# ACB-Light-R1_0-J02.net
KiCad netlist of a schematic drawn in EAGLE
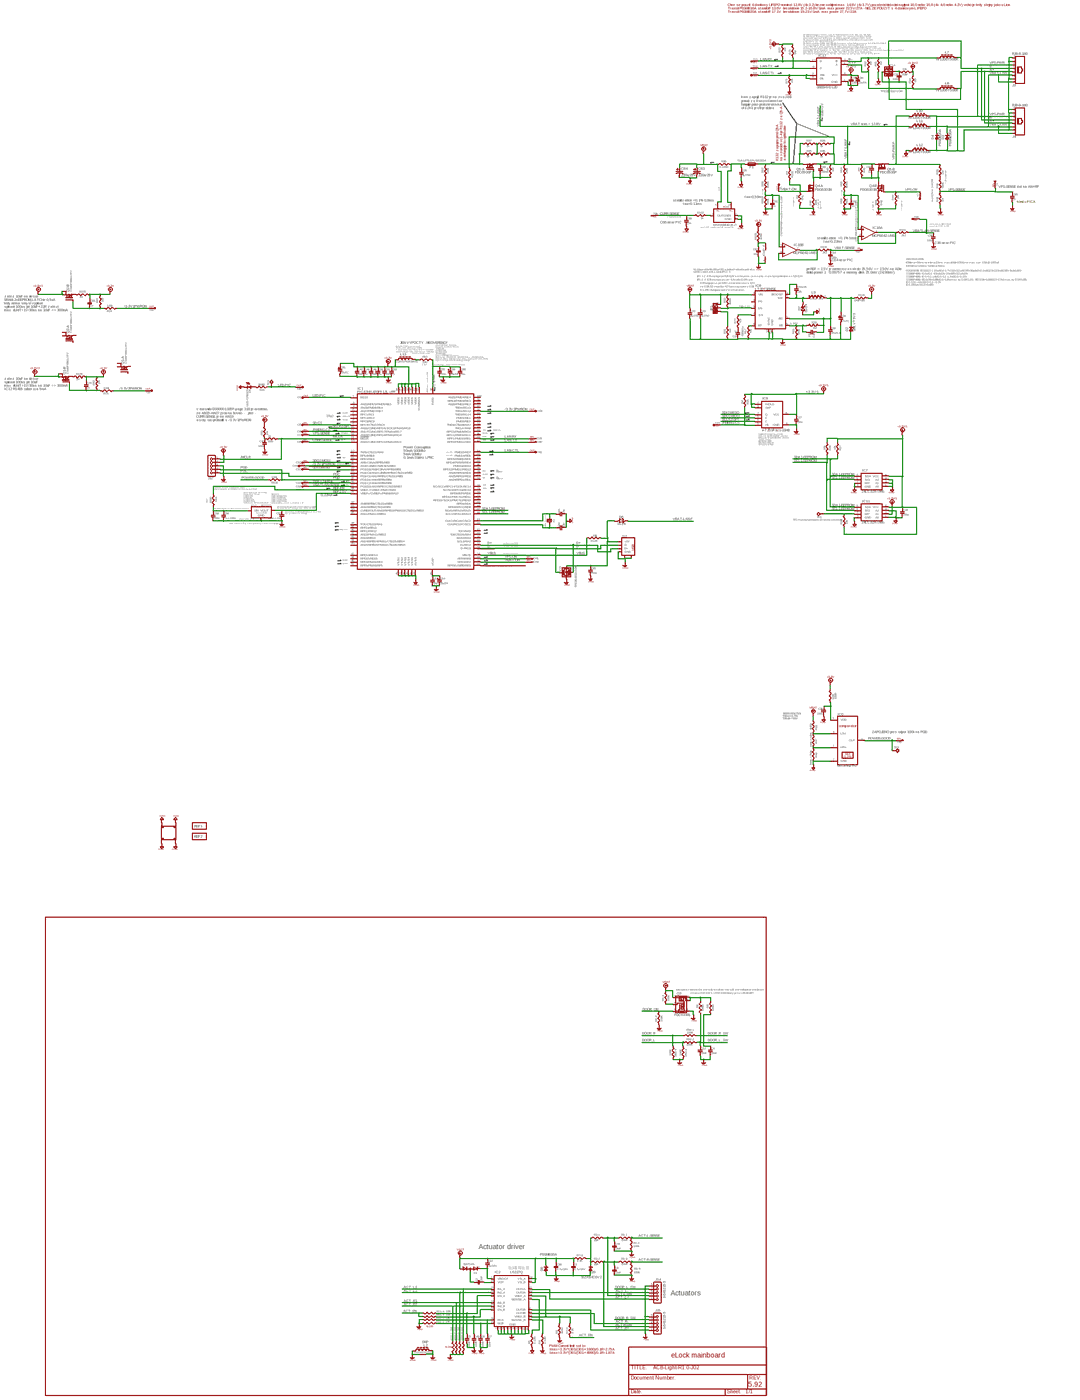
[diagram p0: schematic, sheet 1, overview]
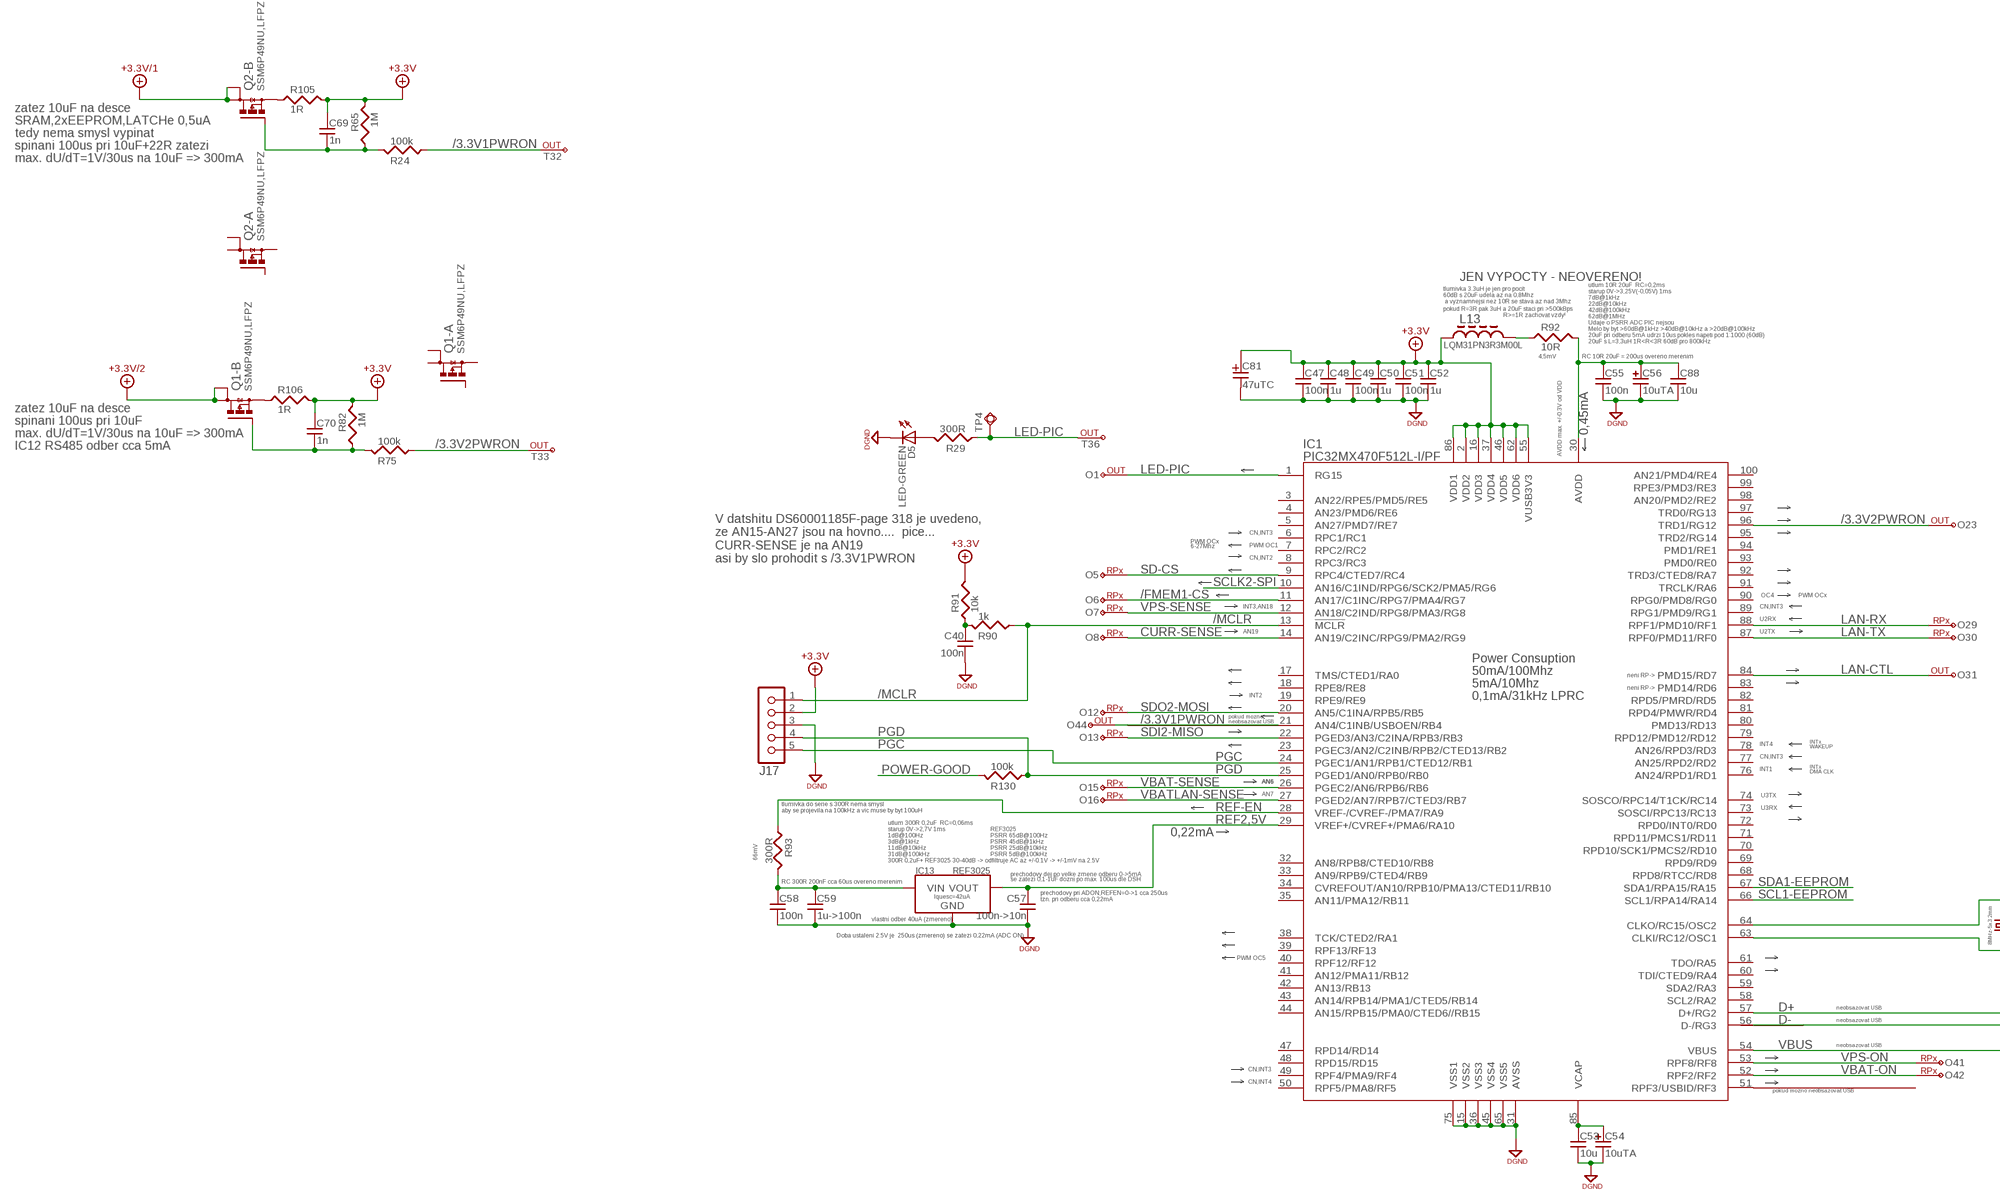
[diagram p1: schematic, sheet 1, part 1 of 5]
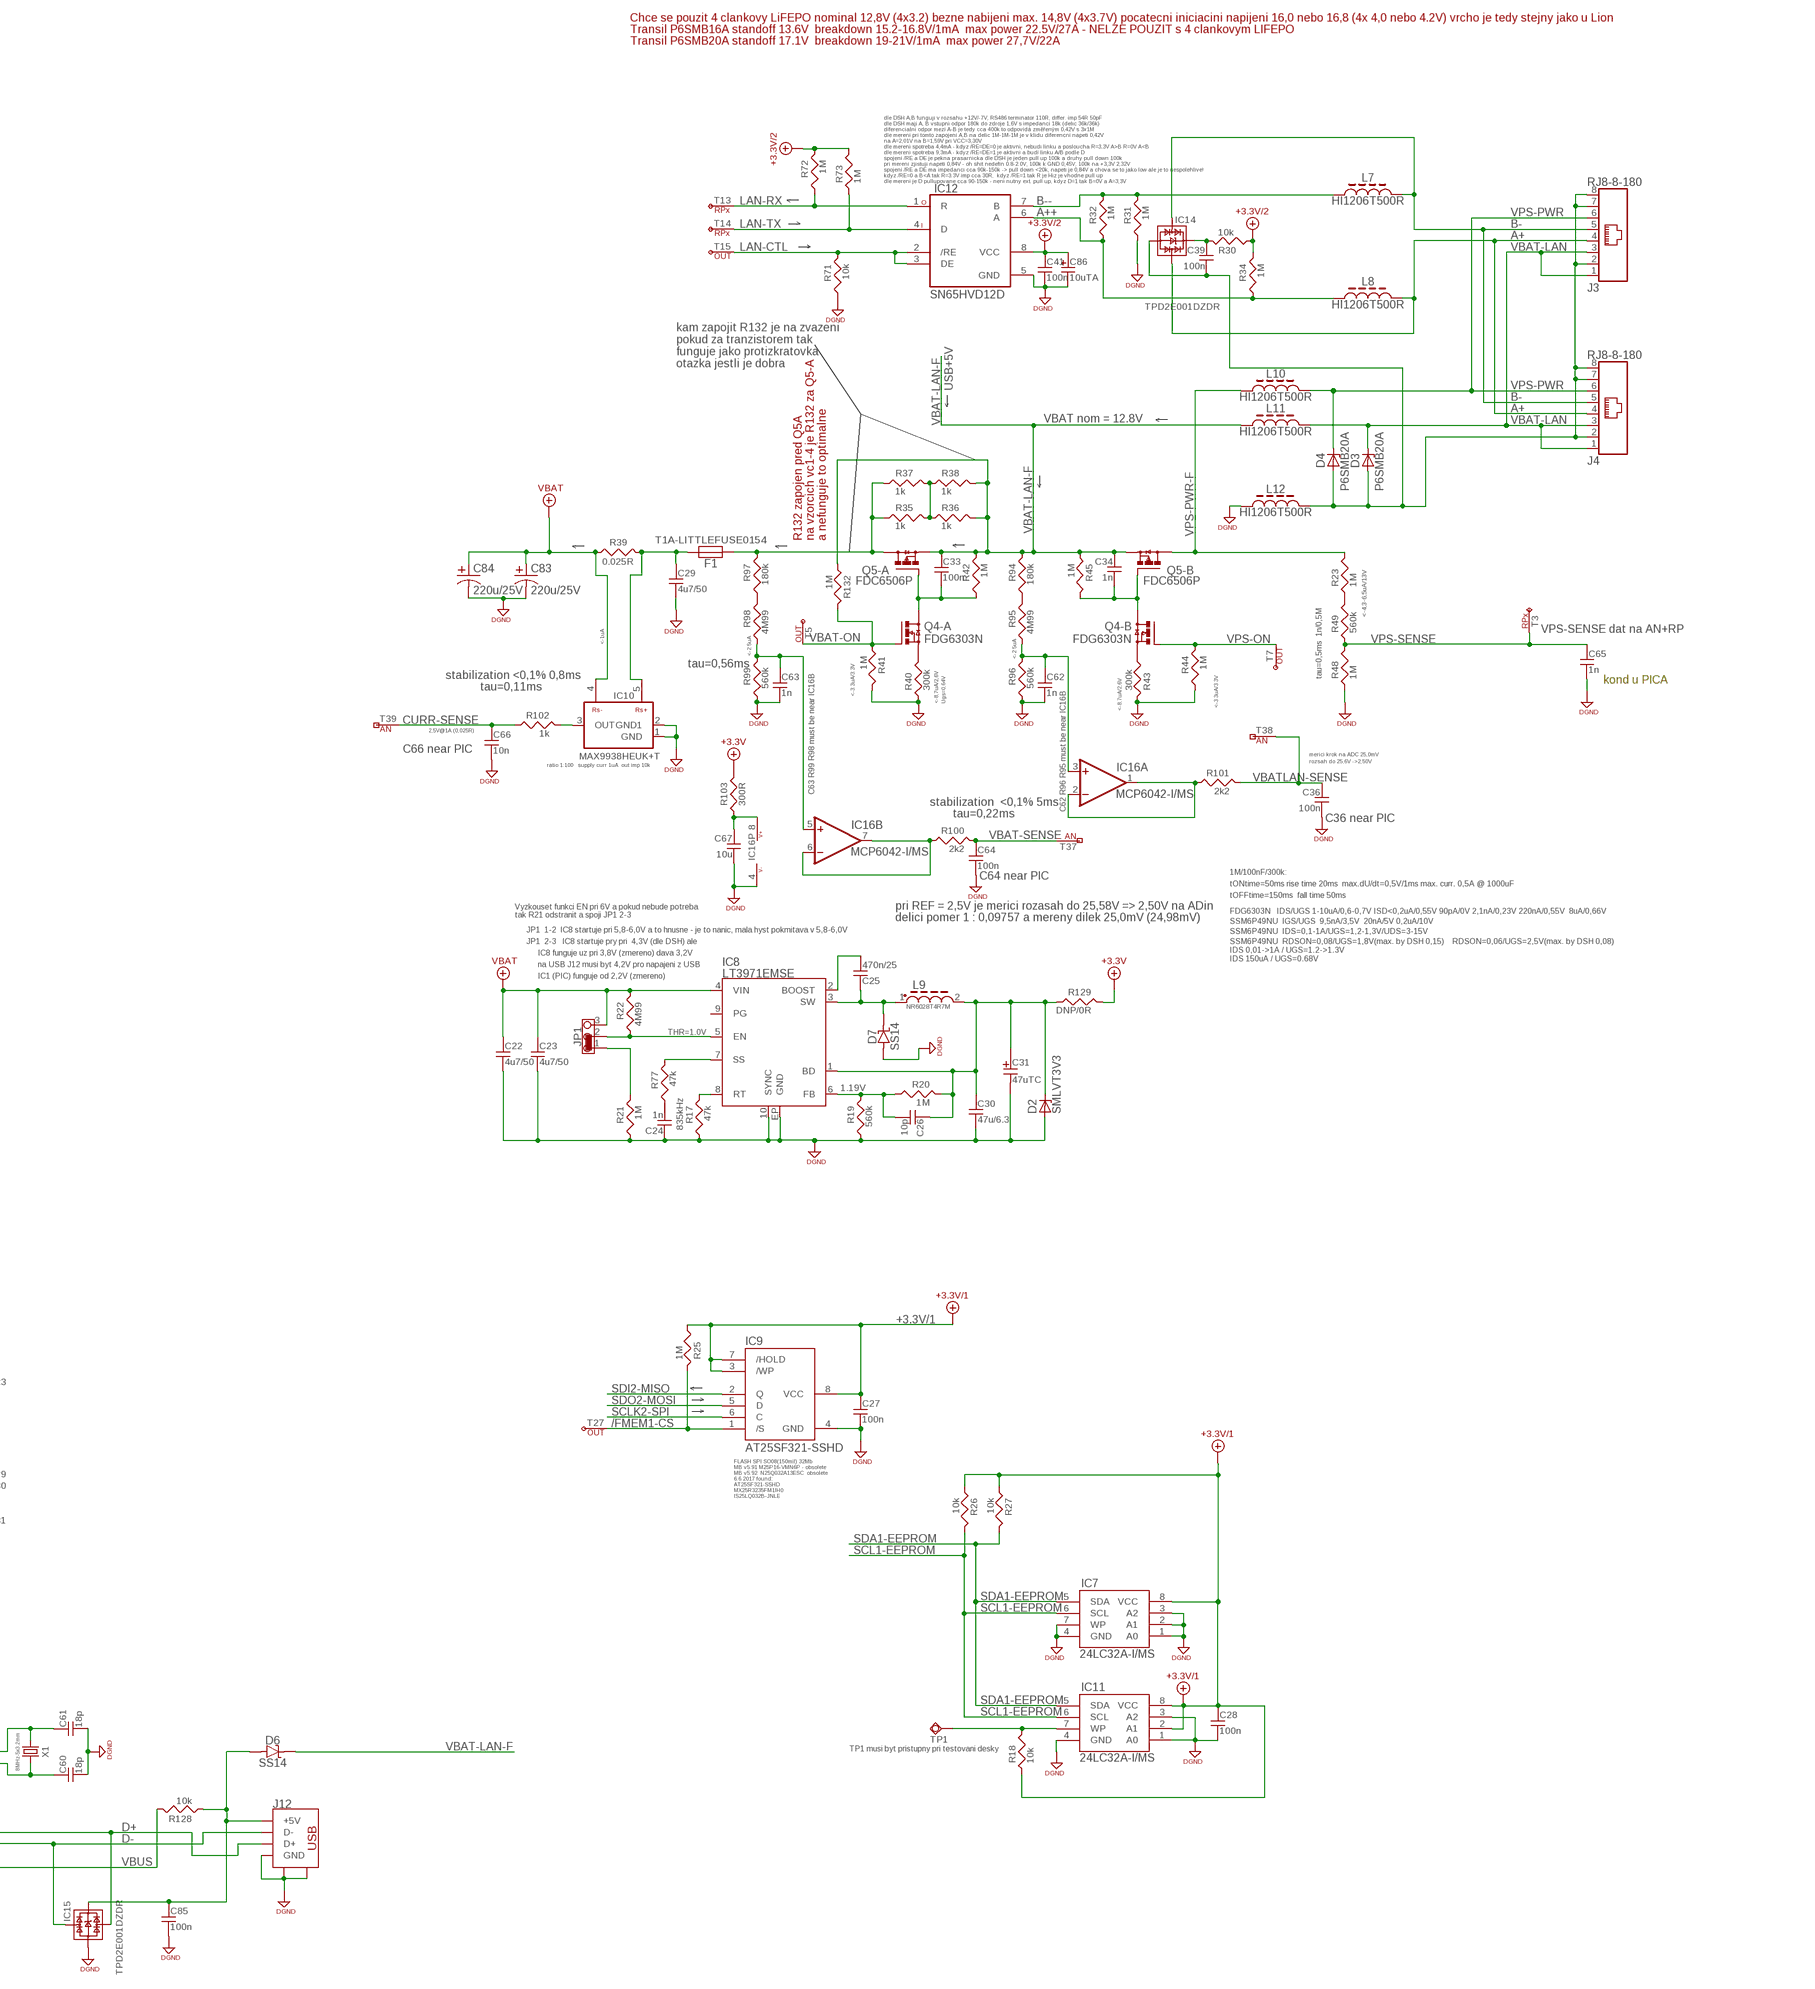
[diagram p2: schematic, sheet 1, part 2 of 5]
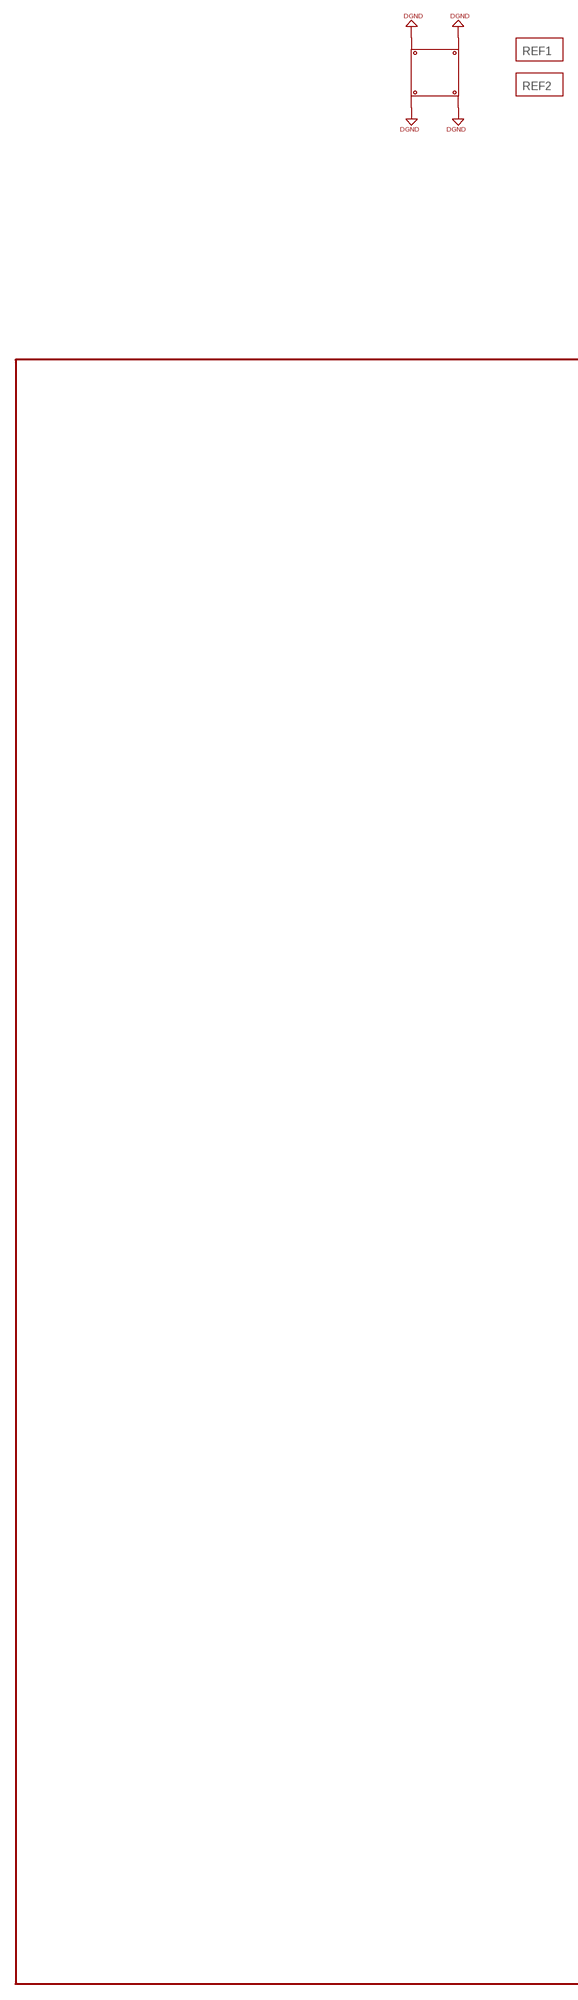
[diagram p3: schematic, sheet 1, part 3 of 5]
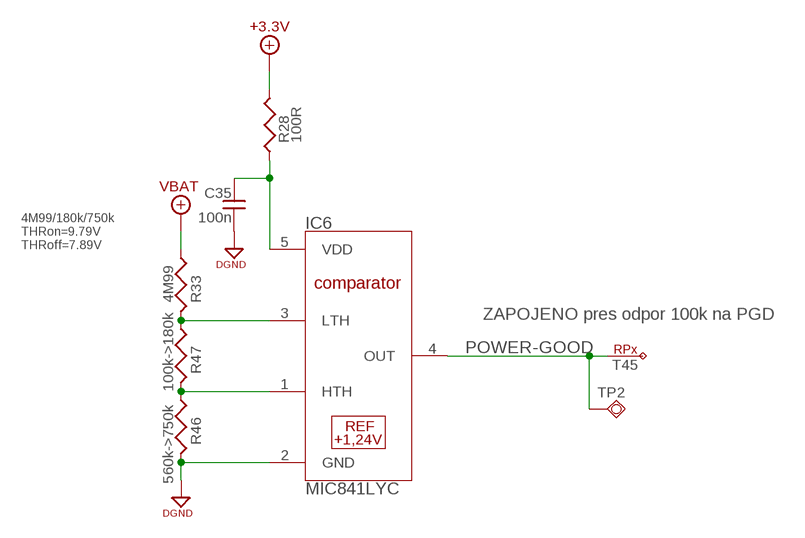
[diagram p4: schematic, sheet 1, part 4 of 5]
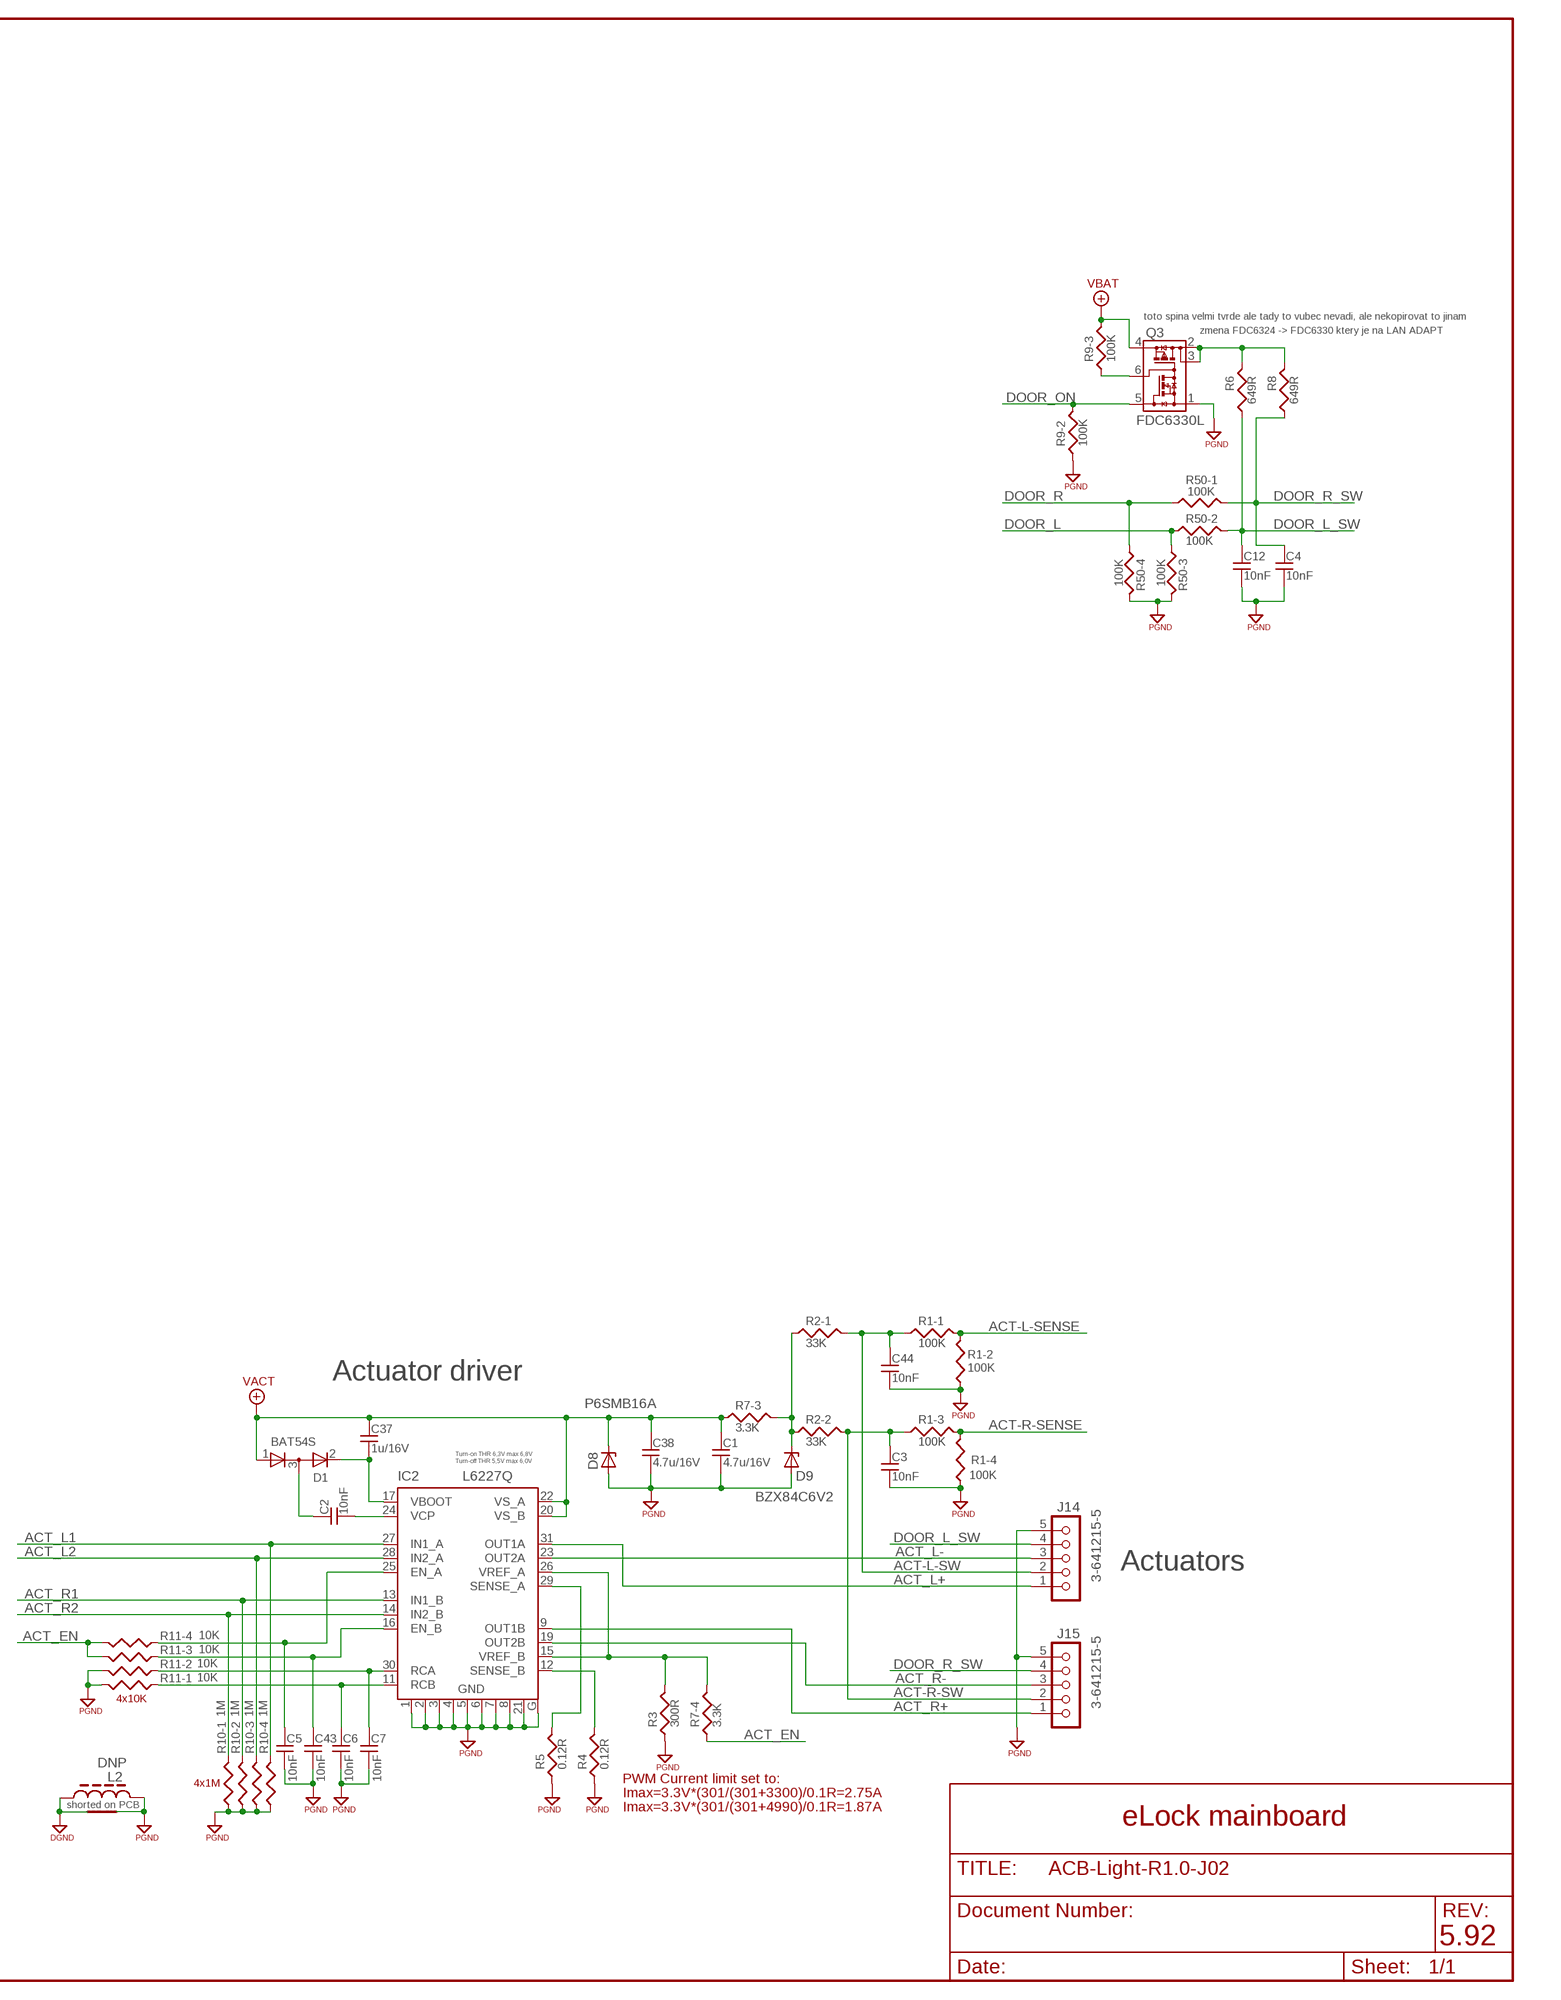
[diagram p5: schematic, sheet 1, part 5 of 5]

(export (version "E")
  (design (tool "Eeschema 10.0.6"))
  (components
    (comp (ref "C1")
      (value "4.7u/16V")
      (footprint "eagle-import:0805")
      (libsource (lib "eagle-import") (part "C-0805"))
    )
    (comp (ref "C2")
      (value "10nF")
      (footprint "eagle-import:0603")
      (libsource (lib "eagle-import") (part "C-0603"))
    )
    (comp (ref "C3")
      (value "10nF")
      (footprint "eagle-import:0603")
      (libsource (lib "eagle-import") (part "C-0603"))
    )
    (comp (ref "C4")
      (value "10nF")
      (footprint "eagle-import:0603")
      (libsource (lib "eagle-import") (part "C-0603"))
    )
    (comp (ref "C5")
      (value "10nF")
      (footprint "eagle-import:0603")
      (libsource (lib "eagle-import") (part "C-0603"))
    )
    (comp (ref "C6")
      (value "10nF")
      (footprint "eagle-import:0603")
      (libsource (lib "eagle-import") (part "C-0603"))
    )
    (comp (ref "C7")
      (value "10nF")
      (footprint "eagle-import:0603")
      (libsource (lib "eagle-import") (part "C-0603"))
    )
    (comp (ref "C12")
      (value "10nF")
      (footprint "eagle-import:0603")
      (libsource (lib "eagle-import") (part "C-0603"))
    )
    (comp (ref "C22")
      (value "4u7/50")
      (footprint "eagle-import:1206")
      (libsource (lib "eagle-import") (part "C-1206"))
    )
    (comp (ref "C23")
      (value "4u7/50")
      (footprint "eagle-import:1206")
      (libsource (lib "eagle-import") (part "C-1206"))
    )
    (comp (ref "C24")
      (value "1n")
      (footprint "eagle-import:0603")
      (libsource (lib "eagle-import") (part "C-0603"))
    )
    (comp (ref "C25")
      (value "470n/25")
      (footprint "eagle-import:0603")
      (libsource (lib "eagle-import") (part "C-0603"))
    )
    (comp (ref "C26")
      (value "10p")
      (footprint "eagle-import:0603")
      (libsource (lib "eagle-import") (part "C-0603"))
    )
    (comp (ref "C27")
      (value "100n")
      (footprint "eagle-import:0603")
      (libsource (lib "eagle-import") (part "C-0603"))
    )
    (comp (ref "C28")
      (value "100n")
      (footprint "eagle-import:0603")
      (libsource (lib "eagle-import") (part "C-0603"))
    )
    (comp (ref "C29")
      (value "4u7/50")
      (footprint "eagle-import:1206")
      (libsource (lib "eagle-import") (part "C-1206"))
    )
    (comp (ref "C30")
      (value "47u/6.3")
      (footprint "eagle-import:1206")
      (libsource (lib "eagle-import") (part "C-1206"))
    )
    (comp (ref "C31")
      (value "47uTC")
      (footprint "eagle-import:CT-C")
      (libsource (lib "eagle-import") (part "CT-C"))
    )
    (comp (ref "C33")
      (value "100n")
      (footprint "eagle-import:0603")
      (libsource (lib "eagle-import") (part "C-0603"))
    )
    (comp (ref "C34")
      (value "1n")
      (footprint "eagle-import:0603")
      (libsource (lib "eagle-import") (part "C-0603"))
    )
    (comp (ref "C35")
      (value "100n")
      (footprint "eagle-import:0603")
      (libsource (lib "eagle-import") (part "C-0603"))
    )
    (comp (ref "C36")
      (value "100n")
      (footprint "eagle-import:0603")
      (libsource (lib "eagle-import") (part "C-0603"))
    )
    (comp (ref "C37")
      (value "1u/16V")
      (footprint "eagle-import:0603")
      (libsource (lib "eagle-import") (part "C-0603"))
    )
    (comp (ref "C38")
      (value "4.7u/16V")
      (footprint "eagle-import:0805")
      (libsource (lib "eagle-import") (part "C-0805"))
    )
    (comp (ref "C39")
      (value "100n")
      (footprint "eagle-import:0603")
      (libsource (lib "eagle-import") (part "C-0603"))
    )
    (comp (ref "C40")
      (value "100n")
      (footprint "eagle-import:0603")
      (libsource (lib "eagle-import") (part "C-0603"))
    )
    (comp (ref "C41")
      (value "100n")
      (footprint "eagle-import:0603")
      (libsource (lib "eagle-import") (part "C-0603"))
    )
    (comp (ref "C43")
      (value "10nF")
      (footprint "eagle-import:0603")
      (libsource (lib "eagle-import") (part "C-0603"))
    )
    (comp (ref "C44")
      (value "10nF")
      (footprint "eagle-import:0603")
      (libsource (lib "eagle-import") (part "C-0603"))
    )
    (comp (ref "C47")
      (value "100n")
      (footprint "eagle-import:0603")
      (libsource (lib "eagle-import") (part "C-0603"))
    )
    (comp (ref "C48")
      (value "1u")
      (footprint "eagle-import:0603")
      (libsource (lib "eagle-import") (part "C-0603"))
    )
    (comp (ref "C49")
      (value "100n")
      (footprint "eagle-import:0603")
      (libsource (lib "eagle-import") (part "C-0603"))
    )
    (comp (ref "C50")
      (value "1u")
      (footprint "eagle-import:0603")
      (libsource (lib "eagle-import") (part "C-0603"))
    )
    (comp (ref "C51")
      (value "100n")
      (footprint "eagle-import:0603")
      (libsource (lib "eagle-import") (part "C-0603"))
    )
    (comp (ref "C52")
      (value "1u")
      (footprint "eagle-import:0603")
      (libsource (lib "eagle-import") (part "C-0603"))
    )
    (comp (ref "C53")
      (value "10u")
      (footprint "eagle-import:0603")
      (libsource (lib "eagle-import") (part "C-0603"))
    )
    (comp (ref "C54")
      (value "10uTA")
      (footprint "eagle-import:1206-POL-C")
      (libsource (lib "eagle-import") (part "CT-1206"))
    )
    (comp (ref "C55")
      (value "100n")
      (footprint "eagle-import:0603")
      (libsource (lib "eagle-import") (part "C-0603"))
    )
    (comp (ref "C56")
      (value "10uTA")
      (footprint "eagle-import:1206-POL-C")
      (libsource (lib "eagle-import") (part "CT-1206"))
    )
    (comp (ref "C57")
      (value "100n->10n")
      (footprint "eagle-import:0603")
      (libsource (lib "eagle-import") (part "C-0603"))
    )
    (comp (ref "C58")
      (value "100n")
      (footprint "eagle-import:0603")
      (libsource (lib "eagle-import") (part "C-0603"))
    )
    (comp (ref "C59")
      (value "1u->100n")
      (footprint "eagle-import:0603")
      (libsource (lib "eagle-import") (part "C-0603"))
    )
    (comp (ref "C60")
      (value "18p")
      (footprint "eagle-import:0603")
      (libsource (lib "eagle-import") (part "C-0603"))
    )
    (comp (ref "C61")
      (value "18p")
      (footprint "eagle-import:0603")
      (libsource (lib "eagle-import") (part "C-0603"))
    )
    (comp (ref "C62")
      (value "1n")
      (footprint "eagle-import:0603")
      (libsource (lib "eagle-import") (part "C-0603"))
    )
    (comp (ref "C63")
      (value "1n")
      (footprint "eagle-import:0603")
      (libsource (lib "eagle-import") (part "C-0603"))
    )
    (comp (ref "C64")
      (value "100n")
      (footprint "eagle-import:0603")
      (libsource (lib "eagle-import") (part "C-0603"))
    )
    (comp (ref "C65")
      (value "1n")
      (footprint "eagle-import:0603")
      (libsource (lib "eagle-import") (part "C-0603"))
    )
    (comp (ref "C66")
      (value "10n")
      (footprint "eagle-import:0603")
      (libsource (lib "eagle-import") (part "C-0603"))
    )
    (comp (ref "C67")
      (value "10u")
      (footprint "eagle-import:0603")
      (libsource (lib "eagle-import") (part "C-0603"))
    )
    (comp (ref "C69")
      (value "1n")
      (footprint "eagle-import:0603")
      (libsource (lib "eagle-import") (part "C-0603"))
    )
    (comp (ref "C70")
      (value "1n")
      (footprint "eagle-import:0603")
      (libsource (lib "eagle-import") (part "C-0603"))
    )
    (comp (ref "C81")
      (value "47uTC")
      (footprint "eagle-import:CT-C")
      (libsource (lib "eagle-import") (part "CT-C"))
    )
    (comp (ref "C83")
      (value "220u/25V")
      (footprint "eagle-import:CAP_8MM_DIA_SMT")
      (libsource (lib "eagle-import") (part "CAP-ELEC-SMD-8MM"))
    )
    (comp (ref "C84")
      (value "220u/25V")
      (footprint "eagle-import:CAP_8MM_DIA_SMT")
      (libsource (lib "eagle-import") (part "CAP-ELEC-SMD-8MM"))
    )
    (comp (ref "C85")
      (value "100n")
      (footprint "eagle-import:0603")
      (libsource (lib "eagle-import") (part "C-0603"))
    )
    (comp (ref "C86")
      (value "10uTA")
      (footprint "eagle-import:1206-POL-C")
      (libsource (lib "eagle-import") (part "CT-1206"))
    )
    (comp (ref "C88")
      (value "10u")
      (footprint "eagle-import:0603")
      (libsource (lib "eagle-import") (part "C-0603"))
    )
    (comp (ref "D1")
      (value "BAT54S")
      (footprint "eagle-import:SOT-23")
      (libsource (lib "eagle-import") (part "BAT54S"))
    )
    (comp (ref "D2")
      (value "SMLVT3V3")
      (footprint "eagle-import:SMA")
      (libsource (lib "eagle-import") (part "SMLVT3V3"))
    )
    (comp (ref "D3")
      (value "P6SMB20A")
      (footprint "eagle-import:SMB")
      (libsource (lib "eagle-import") (part "Littelfuse_P6SMB"))
    )
    (comp (ref "D4")
      (value "P6SMB20A")
      (footprint "eagle-import:SMB")
      (libsource (lib "eagle-import") (part "Littelfuse_P6SMB"))
    )
    (comp (ref "D5")
      (value "LED-GREEN")
      (footprint "eagle-import:0805-POL-D")
      (libsource (lib "eagle-import") (part "LED-0805"))
    )
    (comp (ref "D6")
      (value "SS14")
      (footprint "eagle-import:SMA")
      (libsource (lib "eagle-import") (part "DS-SMA"))
    )
    (comp (ref "D7")
      (value "SS14")
      (footprint "eagle-import:SMA")
      (libsource (lib "eagle-import") (part "DS-SMA"))
    )
    (comp (ref "D8")
      (value "P6SMB16A")
      (footprint "eagle-import:SMB")
      (libsource (lib "eagle-import") (part "P6SMB16A"))
    )
    (comp (ref "D9")
      (value "BZX84C6V2")
      (footprint "eagle-import:SOT-23")
      (libsource (lib "eagle-import") (part "BZX84C6V2"))
    )
    (comp (ref "F1")
      (value "T1A-LITTLEFUSE0154")
      (footprint "eagle-import:LITTLEFUSE0154")
      (libsource (lib "eagle-import") (part "POJISTKA-LITTLEFUSE0154"))
    )
    (comp (ref "IC1")
      (value "PIC32MX470F512L-I/PF")
      (footprint "eagle-import:TQFP100_14X14_0,5MM")
      (libsource (lib "eagle-import") (part "PIC32MX470F512L-I/PF"))
    )
    (comp (ref "IC2")
      (value "L6227Q")
      (footprint "eagle-import:SQFP-S-5X5-32")
      (libsource (lib "eagle-import") (part "L6227Q"))
    )
    (comp (ref "IC6")
      (value "MIC841LYC")
      (footprint "eagle-import:SC-70-5")
      (libsource (lib "eagle-import") (part "MIC841LYC"))
    )
    (comp (ref "IC7")
      (value "24LC32A-I/MS")
      (footprint "eagle-import:MSOP-08")
      (libsource (lib "eagle-import") (part "24-I/MS"))
    )
    (comp (ref "IC8")
      (value "LT3971EMSE")
      (footprint "eagle-import:MSOP10EXP")
      (libsource (lib "eagle-import") (part "LT3971EMSE"))
    )
    (comp (ref "IC9")
      (value "AT25SF321-SSHD")
      (footprint "eagle-import:SO-08")
      (libsource (lib "eagle-import") (part "M25P16-VMN6P"))
    )
    (comp (ref "IC10")
      (value "MAX9938HEUK+T")
      (footprint "eagle-import:SOT23-5")
      (libsource (lib "eagle-import") (part "TSM9938HEUK+T"))
    )
    (comp (ref "IC11")
      (value "24LC32A-I/MS")
      (footprint "eagle-import:MSOP-08")
      (libsource (lib "eagle-import") (part "24-I/MS"))
    )
    (comp (ref "IC12")
      (value "SN65HVD12D")
      (footprint "eagle-import:SO08")
      (libsource (lib "eagle-import") (part "SN65HVD3082ED"))
    )
    (comp (ref "IC13")
      (value "REF3025")
      (footprint "eagle-import:SOT23")
      (libsource (lib "eagle-import") (part "REF3025"))
    )
    (comp (ref "IC14")
      (value "TPD2E001DZDR")
      (footprint "eagle-import:SOT-143")
      (libsource (lib "eagle-import") (part "SR05.TCT"))
    )
    (comp (ref "IC15")
      (value "TPD2E001DZDR")
      (footprint "eagle-import:SOT-143")
      (libsource (lib "eagle-import") (part "SR05.TCT"))
    )
    (comp (ref "IC16")
      (value "MCP6042-I/MS")
      (footprint "eagle-import:MSOP-08")
      (libsource (lib "eagle-import") (part "MCP6042-I/MS"))
    )
    (comp (ref "J3")
      (value "RJ8-8-180")
      (footprint "eagle-import:RJ8-8-180")
      (libsource (lib "eagle-import") (part "RJ8-8-180"))
    )
    (comp (ref "J4")
      (value "RJ8-8-180")
      (footprint "eagle-import:RJ8-8-180")
      (libsource (lib "eagle-import") (part "RJ8-8-180"))
    )
    (comp (ref "J12")
      (value "USB_A_180")
      (footprint "eagle-import:USB_B_180")
      (libsource (lib "eagle-import") (part "USB_B_180"))
    )
    (comp (ref "J14")
      (value "3-641215-5")
      (footprint "eagle-import:3-641215-5")
      (libsource (lib "eagle-import") (part "3-641215-5"))
    )
    (comp (ref "J15")
      (value "3-641215-5")
      (footprint "eagle-import:3-641215-5")
      (libsource (lib "eagle-import") (part "3-641215-5"))
    )
    (comp (ref "J17")
      (value "DNP-open-hole")
      (footprint "eagle-import:MA05-1")
      (libsource (lib "eagle-import") (part "MA05-1"))
    )
    (comp (ref "JP1")
      (value "JP3CLOSE12")
      (footprint "eagle-import:JP3CLOSE12")
      (libsource (lib "eagle-import") (part "JP3CLOSE12"))
    )
    (comp (ref "L2")
      (value "DNP")
      (footprint "eagle-import:0805-0RTOP")
      (libsource (lib "eagle-import") (part "L-0805-0R"))
    )
    (comp (ref "L7")
      (value "HI1206T500R")
      (footprint "eagle-import:1206")
      (libsource (lib "eagle-import") (part "L-1206"))
    )
    (comp (ref "L8")
      (value "HI1206T500R")
      (footprint "eagle-import:1206")
      (libsource (lib "eagle-import") (part "L-1206"))
    )
    (comp (ref "L9")
      (value "NR6028T4R7M")
      (footprint "eagle-import:NR6028")
      (libsource (lib "eagle-import") (part "NR6028"))
    )
    (comp (ref "L10")
      (value "HI1206T500R")
      (footprint "eagle-import:1206")
      (libsource (lib "eagle-import") (part "L-1206"))
    )
    (comp (ref "L11")
      (value "HI1206T500R")
      (footprint "eagle-import:1206")
      (libsource (lib "eagle-import") (part "L-1206"))
    )
    (comp (ref "L12")
      (value "HI1206T500R")
      (footprint "eagle-import:1206")
      (libsource (lib "eagle-import") (part "L-1206"))
    )
    (comp (ref "L13")
      (value "LQM31PN3R3M00L")
      (footprint "eagle-import:1206")
      (libsource (lib "eagle-import") (part "L-1206"))
    )
    (comp (ref "O1")
      (value "PIC-OUT")
      (footprint "eagle-import:TEMP-PAD")
      (libsource (lib "eagle-import") (part "PIC-OUT"))
    )
    (comp (ref "O5")
      (value "PIC-RPX")
      (footprint "eagle-import:TEMP-PAD")
      (libsource (lib "eagle-import") (part "PIC-RPX"))
    )
    (comp (ref "O6")
      (value "PIC-RPX")
      (footprint "eagle-import:TEMP-PAD")
      (libsource (lib "eagle-import") (part "PIC-RPX"))
    )
    (comp (ref "O7")
      (value "PIC-RPX")
      (footprint "eagle-import:TEMP-PAD")
      (libsource (lib "eagle-import") (part "PIC-RPX"))
    )
    (comp (ref "O8")
      (value "PIC-RPX")
      (footprint "eagle-import:TEMP-PAD")
      (libsource (lib "eagle-import") (part "PIC-RPX"))
    )
    (comp (ref "O12")
      (value "PIC-RPX")
      (footprint "eagle-import:TEMP-PAD")
      (libsource (lib "eagle-import") (part "PIC-RPX"))
    )
    (comp (ref "O13")
      (value "PIC-RPX")
      (footprint "eagle-import:TEMP-PAD")
      (libsource (lib "eagle-import") (part "PIC-RPX"))
    )
    (comp (ref "O15")
      (value "PIC-RPX")
      (footprint "eagle-import:TEMP-PAD")
      (libsource (lib "eagle-import") (part "PIC-RPX"))
    )
    (comp (ref "O16")
      (value "PIC-RPX")
      (footprint "eagle-import:TEMP-PAD")
      (libsource (lib "eagle-import") (part "PIC-RPX"))
    )
    (comp (ref "O23")
      (value "PIC-OUT")
      (footprint "eagle-import:TEMP-PAD")
      (libsource (lib "eagle-import") (part "PIC-OUT"))
    )
    (comp (ref "O29")
      (value "PIC-RPX")
      (footprint "eagle-import:TEMP-PAD")
      (libsource (lib "eagle-import") (part "PIC-RPX"))
    )
    (comp (ref "O30")
      (value "PIC-RPX")
      (footprint "eagle-import:TEMP-PAD")
      (libsource (lib "eagle-import") (part "PIC-RPX"))
    )
    (comp (ref "O31")
      (value "PIC-OUT")
      (footprint "eagle-import:TEMP-PAD")
      (libsource (lib "eagle-import") (part "PIC-OUT"))
    )
    (comp (ref "O41")
      (value "PIC-RPX")
      (footprint "eagle-import:TEMP-PAD")
      (libsource (lib "eagle-import") (part "PIC-RPX"))
    )
    (comp (ref "O42")
      (value "PIC-RPX")
      (footprint "eagle-import:TEMP-PAD")
      (libsource (lib "eagle-import") (part "PIC-RPX"))
    )
    (comp (ref "O44")
      (value "PIC-OUT")
      (footprint "eagle-import:TEMP-PAD")
      (libsource (lib "eagle-import") (part "PIC-OUT"))
    )
    (comp (ref "PCB1")
      (value "PCB-ACB")
      (footprint "eagle-import:PCB-ACB")
      (libsource (lib "eagle-import") (part "PCB-ACB-1"))
    )
    (comp (ref "Q1")
      (value "SSM6P49NU,LFPZ")
      (footprint "eagle-import:MICRO_FET")
      (libsource (lib "eagle-import") (part "SSM6P49PZNU,LF"))
    )
    (comp (ref "Q2")
      (value "SSM6P49NU,LFPZ")
      (footprint "eagle-import:MICRO_FET")
      (libsource (lib "eagle-import") (part "SSM6P49PZNU,LF"))
    )
    (comp (ref "Q3")
      (value "FDC6330L")
      (footprint "eagle-import:SSOT-6")
      (libsource (lib "eagle-import") (part "FDC6324L"))
    )
    (comp (ref "Q4")
      (value "FDG6303N")
      (footprint "eagle-import:SC70-6")
      (libsource (lib "eagle-import") (part "FDG6303N"))
    )
    (comp (ref "Q5")
      (value "FDC6506P")
      (footprint "eagle-import:SSOT-6@1")
      (libsource (lib "eagle-import") (part "FDC6506D"))
    )
    (comp (ref "R1")
      (value "100K")
      (footprint "eagle-import:0603-ARRAY")
      (libsource (lib "eagle-import") (part "EXB-38"))
    )
    (comp (ref "R2")
      (value "33K")
      (footprint "eagle-import:0603-ARRAY")
      (libsource (lib "eagle-import") (part "EXB-38"))
    )
    (comp (ref "R3")
      (value "300R")
      (footprint "eagle-import:0603")
      (libsource (lib "eagle-import") (part "R-0603"))
    )
    (comp (ref "R4")
      (value "0.12R")
      (footprint "eagle-import:0805")
      (libsource (lib "eagle-import") (part "R-0805"))
    )
    (comp (ref "R5")
      (value "0.12R")
      (footprint "eagle-import:0805")
      (libsource (lib "eagle-import") (part "R-0805"))
    )
    (comp (ref "R6")
      (value "649R")
      (footprint "eagle-import:0603")
      (libsource (lib "eagle-import") (part "R-0603"))
    )
    (comp (ref "R7")
      (value "3.3K")
      (footprint "eagle-import:0603-ARRAY")
      (libsource (lib "eagle-import") (part "EXB-38"))
    )
    (comp (ref "R8")
      (value "649R")
      (footprint "eagle-import:0603")
      (libsource (lib "eagle-import") (part "R-0603"))
    )
    (comp (ref "R9")
      (value "100K")
      (footprint "eagle-import:0603-ARRAY")
      (libsource (lib "eagle-import") (part "EXB-38"))
    )
    (comp (ref "R10")
      (value "1M")
      (footprint "eagle-import:0603-ARRAY")
      (libsource (lib "eagle-import") (part "EXB-38"))
    )
    (comp (ref "R11")
      (value "10K")
      (footprint "eagle-import:0603-ARRAY")
      (libsource (lib "eagle-import") (part "EXB-38"))
    )
    (comp (ref "R17")
      (value "47k")
      (footprint "eagle-import:0603")
      (libsource (lib "eagle-import") (part "R-0603"))
    )
    (comp (ref "R18")
      (value "10k")
      (footprint "eagle-import:0603")
      (libsource (lib "eagle-import") (part "R-0603"))
    )
    (comp (ref "R19")
      (value "560k")
      (footprint "eagle-import:0603")
      (libsource (lib "eagle-import") (part "R-0603"))
    )
    (comp (ref "R20")
      (value "1M")
      (footprint "eagle-import:0603")
      (libsource (lib "eagle-import") (part "R-0603"))
    )
    (comp (ref "R21")
      (value "1M")
      (footprint "eagle-import:0603")
      (libsource (lib "eagle-import") (part "R-0603"))
    )
    (comp (ref "R22")
      (value "4M99")
      (footprint "eagle-import:0603")
      (libsource (lib "eagle-import") (part "R-0603"))
    )
    (comp (ref "R23")
      (value "1M")
      (footprint "eagle-import:0603")
      (libsource (lib "eagle-import") (part "R-0603"))
    )
    (comp (ref "R24")
      (value "100k")
      (footprint "eagle-import:0603")
      (libsource (lib "eagle-import") (part "R-0603"))
    )
    (comp (ref "R25")
      (value "1M")
      (footprint "eagle-import:0603")
      (libsource (lib "eagle-import") (part "R-0603"))
    )
    (comp (ref "R26")
      (value "10k")
      (footprint "eagle-import:0603")
      (libsource (lib "eagle-import") (part "R-0603"))
    )
    (comp (ref "R27")
      (value "10k")
      (footprint "eagle-import:0603")
      (libsource (lib "eagle-import") (part "R-0603"))
    )
    (comp (ref "R28")
      (value "100R")
      (footprint "eagle-import:0603")
      (libsource (lib "eagle-import") (part "R-0603"))
    )
    (comp (ref "R29")
      (value "300R")
      (footprint "eagle-import:0603")
      (libsource (lib "eagle-import") (part "R-0603"))
    )
    (comp (ref "R30")
      (value "10k")
      (footprint "eagle-import:0603")
      (libsource (lib "eagle-import") (part "R-0603"))
    )
    (comp (ref "R31")
      (value "1M")
      (footprint "eagle-import:0603")
      (libsource (lib "eagle-import") (part "R-0603"))
    )
    (comp (ref "R32")
      (value "1M")
      (footprint "eagle-import:0603")
      (libsource (lib "eagle-import") (part "R-0603"))
    )
    (comp (ref "R33")
      (value "4M99")
      (footprint "eagle-import:0603")
      (libsource (lib "eagle-import") (part "R-0603"))
    )
    (comp (ref "R34")
      (value "1M")
      (footprint "eagle-import:0603")
      (libsource (lib "eagle-import") (part "R-0603"))
    )
    (comp (ref "R35")
      (value "1k")
      (footprint "eagle-import:0805")
      (libsource (lib "eagle-import") (part "R-0805"))
    )
    (comp (ref "R36")
      (value "1k")
      (footprint "eagle-import:0805")
      (libsource (lib "eagle-import") (part "R-0805"))
    )
    (comp (ref "R37")
      (value "1k")
      (footprint "eagle-import:0805")
      (libsource (lib "eagle-import") (part "R-0805"))
    )
    (comp (ref "R38")
      (value "1k")
      (footprint "eagle-import:0805")
      (libsource (lib "eagle-import") (part "R-0805"))
    )
    (comp (ref "R39")
      (value "0.025R")
      (footprint "eagle-import:0805")
      (libsource (lib "eagle-import") (part "R-0805"))
    )
    (comp (ref "R40")
      (value "300k")
      (footprint "eagle-import:0603")
      (libsource (lib "eagle-import") (part "R-0603"))
    )
    (comp (ref "R41")
      (value "1M")
      (footprint "eagle-import:0603")
      (libsource (lib "eagle-import") (part "R-0603"))
    )
    (comp (ref "R42")
      (value "1M")
      (footprint "eagle-import:0603")
      (libsource (lib "eagle-import") (part "R-0603"))
    )
    (comp (ref "R43")
      (value "300k")
      (footprint "eagle-import:0603")
      (libsource (lib "eagle-import") (part "R-0603"))
    )
    (comp (ref "R44")
      (value "1M")
      (footprint "eagle-import:0603")
      (libsource (lib "eagle-import") (part "R-0603"))
    )
    (comp (ref "R45")
      (value "1M")
      (footprint "eagle-import:0603")
      (libsource (lib "eagle-import") (part "R-0603"))
    )
    (comp (ref "R46")
      (value "560k->750k")
      (footprint "eagle-import:0603")
      (libsource (lib "eagle-import") (part "R-0603"))
    )
    (comp (ref "R47")
      (value "100k->180k")
      (footprint "eagle-import:0603")
      (libsource (lib "eagle-import") (part "R-0603"))
    )
    (comp (ref "R48")
      (value "1M")
      (footprint "eagle-import:0603")
      (libsource (lib "eagle-import") (part "R-0603"))
    )
    (comp (ref "R49")
      (value "560k")
      (footprint "eagle-import:0603")
      (libsource (lib "eagle-import") (part "R-0603"))
    )
    (comp (ref "R50")
      (value "100K")
      (footprint "eagle-import:0603-ARRAY")
      (libsource (lib "eagle-import") (part "EXB-38"))
    )
    (comp (ref "R65")
      (value "1M")
      (footprint "eagle-import:0603")
      (libsource (lib "eagle-import") (part "R-0603"))
    )
    (comp (ref "R71")
      (value "10k")
      (footprint "eagle-import:0603")
      (libsource (lib "eagle-import") (part "R-0603"))
    )
    (comp (ref "R72")
      (value "1M")
      (footprint "eagle-import:0603")
      (libsource (lib "eagle-import") (part "R-0603"))
    )
    (comp (ref "R73")
      (value "1M")
      (footprint "eagle-import:0603")
      (libsource (lib "eagle-import") (part "R-0603"))
    )
    (comp (ref "R75")
      (value "100k")
      (footprint "eagle-import:0603")
      (libsource (lib "eagle-import") (part "R-0603"))
    )
    (comp (ref "R77")
      (value "47k")
      (footprint "eagle-import:0603")
      (libsource (lib "eagle-import") (part "R-0603"))
    )
    (comp (ref "R82")
      (value "1M")
      (footprint "eagle-import:0603")
      (libsource (lib "eagle-import") (part "R-0603"))
    )
    (comp (ref "R90")
      (value "1k")
      (footprint "eagle-import:0603")
      (libsource (lib "eagle-import") (part "R-0603"))
    )
    (comp (ref "R91")
      (value "10k")
      (footprint "eagle-import:0603")
      (libsource (lib "eagle-import") (part "R-0603"))
    )
    (comp (ref "R92")
      (value "10R")
      (footprint "eagle-import:0603")
      (libsource (lib "eagle-import") (part "R-0603"))
    )
    (comp (ref "R93")
      (value "300R")
      (footprint "eagle-import:0603")
      (libsource (lib "eagle-import") (part "R-0603"))
    )
    (comp (ref "R94")
      (value "180k")
      (footprint "eagle-import:0603")
      (libsource (lib "eagle-import") (part "R-0603"))
    )
    (comp (ref "R95")
      (value "4M99")
      (footprint "eagle-import:0603")
      (libsource (lib "eagle-import") (part "R-0603"))
    )
    (comp (ref "R96")
      (value "560k")
      (footprint "eagle-import:0603")
      (libsource (lib "eagle-import") (part "R-0603"))
    )
    (comp (ref "R97")
      (value "180k")
      (footprint "eagle-import:0603")
      (libsource (lib "eagle-import") (part "R-0603"))
    )
    (comp (ref "R98")
      (value "4M99")
      (footprint "eagle-import:0603")
      (libsource (lib "eagle-import") (part "R-0603"))
    )
    (comp (ref "R99")
      (value "560k")
      (footprint "eagle-import:0603")
      (libsource (lib "eagle-import") (part "R-0603"))
    )
    (comp (ref "R100")
      (value "2k2")
      (footprint "eagle-import:0603")
      (libsource (lib "eagle-import") (part "R-0603"))
    )
    (comp (ref "R101")
      (value "2k2")
      (footprint "eagle-import:0603")
      (libsource (lib "eagle-import") (part "R-0603"))
    )
    (comp (ref "R102")
      (value "1k")
      (footprint "eagle-import:0603")
      (libsource (lib "eagle-import") (part "R-0603"))
    )
    (comp (ref "R103")
      (value "300R")
      (footprint "eagle-import:0603")
      (libsource (lib "eagle-import") (part "R-0603"))
    )
    (comp (ref "R105")
      (value "1R")
      (footprint "eagle-import:0805")
      (libsource (lib "eagle-import") (part "R-0805"))
    )
    (comp (ref "R106")
      (value "1R")
      (footprint "eagle-import:0805")
      (libsource (lib "eagle-import") (part "R-0805"))
    )
    (comp (ref "R128")
      (value "10k")
      (footprint "eagle-import:0603")
      (libsource (lib "eagle-import") (part "R-0603"))
    )
    (comp (ref "R129")
      (value "DNP/0R")
      (footprint "eagle-import:0603")
      (libsource (lib "eagle-import") (part "R-0603"))
    )
    (comp (ref "R130")
      (value "100k")
      (footprint "eagle-import:0603")
      (libsource (lib "eagle-import") (part "R-0603"))
    )
    (comp (ref "R132")
      (value "1M")
      (footprint "eagle-import:0603")
      (libsource (lib "eagle-import") (part "R-0603"))
    )
    (comp (ref "REF1")
      (value "REF")
      (footprint "eagle-import:REF")
      (libsource (lib "eagle-import") (part "REF"))
    )
    (comp (ref "REF2")
      (value "REF")
      (footprint "eagle-import:REF")
      (libsource (lib "eagle-import") (part "REF"))
    )
    (comp (ref "T3")
      (value "PIC-RPX")
      (footprint "eagle-import:TEMP-PAD")
      (libsource (lib "eagle-import") (part "PIC-RPX"))
    )
    (comp (ref "T5")
      (value "PIC-OUT")
      (footprint "eagle-import:TEMP-PAD")
      (libsource (lib "eagle-import") (part "PIC-OUT"))
    )
    (comp (ref "T7")
      (value "PIC-OUT")
      (footprint "eagle-import:TEMP-PAD")
      (libsource (lib "eagle-import") (part "PIC-OUT"))
    )
    (comp (ref "T13")
      (value "PIC-RPX")
      (footprint "eagle-import:TEMP-PAD")
      (libsource (lib "eagle-import") (part "PIC-RPX"))
    )
    (comp (ref "T14")
      (value "PIC-RPX")
      (footprint "eagle-import:TEMP-PAD")
      (libsource (lib "eagle-import") (part "PIC-RPX"))
    )
    (comp (ref "T15")
      (value "PIC-OUT")
      (footprint "eagle-import:TEMP-PAD")
      (libsource (lib "eagle-import") (part "PIC-OUT"))
    )
    (comp (ref "T27")
      (value "PIC-OUT")
      (footprint "eagle-import:TEMP-PAD")
      (libsource (lib "eagle-import") (part "PIC-OUT"))
    )
    (comp (ref "T32")
      (value "PIC-OUT")
      (footprint "eagle-import:TEMP-PAD")
      (libsource (lib "eagle-import") (part "PIC-OUT"))
    )
    (comp (ref "T33")
      (value "PIC-OUT")
      (footprint "eagle-import:TEMP-PAD")
      (libsource (lib "eagle-import") (part "PIC-OUT"))
    )
    (comp (ref "T36")
      (value "PIC-OUT")
      (footprint "eagle-import:TEMP-PAD")
      (libsource (lib "eagle-import") (part "PIC-OUT"))
    )
    (comp (ref "T37")
      (value "PIN-AN")
      (footprint "eagle-import:TEMP-PAD")
      (libsource (lib "eagle-import") (part "PIN-AN"))
    )
    (comp (ref "T38")
      (value "PIN-AN")
      (footprint "eagle-import:TEMP-PAD")
      (libsource (lib "eagle-import") (part "PIN-AN"))
    )
    (comp (ref "T39")
      (value "PIN-AN")
      (footprint "eagle-import:TEMP-PAD")
      (libsource (lib "eagle-import") (part "PIN-AN"))
    )
    (comp (ref "T45")
      (value "PIC-RPX")
      (footprint "eagle-import:TEMP-PAD")
      (libsource (lib "eagle-import") (part "PIC-RPX"))
    )
    (comp (ref "TP1")
      (value "DNP-TestPoint")
      (footprint "eagle-import:SMD_ROUND_1MM")
      (libsource (lib "eagle-import") (part "ROUND_SMD1MM"))
    )
    (comp (ref "TP2")
      (value "DNP-TestPoint")
      (footprint "eagle-import:TH_ROUND_14MM08MM")
      (libsource (lib "eagle-import") (part "ROUND_SMDTH1.4MM"))
    )
    (comp (ref "TP4")
      (value "DNP-TestPoint")
      (footprint "eagle-import:TH_ROUND_14MM08MM")
      (libsource (lib "eagle-import") (part "ROUND_SMDTH1.4MM"))
    )
    (comp (ref "X1")
      (value "8MHz-5x3.2mm")
      (footprint "eagle-import:7B")
      (libsource (lib "eagle-import") (part "XTAL-7B"))
    )
  )
  (nets
    (net (code "1") (name "+3.3V") (class "Default")
      (node (ref "C47") (pin "1") (pinfunction "1_1") (pintype "passive"))
      (node (ref "C48") (pin "1") (pinfunction "1_1") (pintype "passive"))
      (node (ref "C49") (pin "1") (pinfunction "1_1") (pintype "passive"))
      (node (ref "C50") (pin "1") (pinfunction "1_1") (pintype "passive"))
      (node (ref "C51") (pin "1") (pinfunction "1_1") (pintype "passive"))
      (node (ref "C52") (pin "1") (pinfunction "1_1") (pintype "passive"))
      (node (ref "C69") (pin "1") (pinfunction "1_1") (pintype "passive"))
      (node (ref "C70") (pin "1") (pinfunction "1_1") (pintype "passive"))
      (node (ref "C81") (pin "+") (pinfunction "+_+") (pintype "passive"))
      (node (ref "IC1") (pin "16") (pinfunction "VDD3_16") (pintype "input"))
      (node (ref "IC1") (pin "2") (pinfunction "VDD2_2") (pintype "input"))
      (node (ref "IC1") (pin "37") (pinfunction "VDD4_37") (pintype "input"))
      (node (ref "IC1") (pin "46") (pinfunction "VDD5_46") (pintype "input"))
      (node (ref "IC1") (pin "55") (pinfunction "VUSB3V3_55") (pintype "input"))
      (node (ref "IC1") (pin "62") (pinfunction "VDD6_62") (pintype "input"))
      (node (ref "IC1") (pin "86") (pinfunction "VDD1_86") (pintype "input"))
      (node (ref "J17") (pin "2") (pinfunction "2_2") (pintype "passive"))
      (node (ref "L13") (pin "1") (pinfunction "1_1") (pintype "passive"))
      (node (ref "R103") (pin "2") (pinfunction "2_2") (pintype "passive"))
      (node (ref "R105") (pin "2") (pinfunction "2_2") (pintype "passive"))
      (node (ref "R106") (pin "2") (pinfunction "2_2") (pintype "passive"))
      (node (ref "R129") (pin "1") (pinfunction "1_1") (pintype "passive"))
      (node (ref "R28") (pin "2") (pinfunction "2_2") (pintype "passive"))
      (node (ref "R65") (pin "1") (pinfunction "1_1") (pintype "passive"))
      (node (ref "R82") (pin "1") (pinfunction "1_1") (pintype "passive"))
      (node (ref "R91") (pin "2") (pinfunction "2_2") (pintype "passive"))
    )
    (net (code "2") (name "+3.3V{slash}1") (class "Default")
      (node (ref "C27") (pin "1") (pinfunction "1_1") (pintype "passive"))
      (node (ref "C28") (pin "1") (pinfunction "1_1") (pintype "passive"))
      (node (ref "IC11") (pin "2") (pinfunction "A1_2") (pintype "input"))
      (node (ref "IC11") (pin "8") (pinfunction "VCC_8") (pintype "input"))
      (node (ref "IC7") (pin "8") (pinfunction "VCC_8") (pintype "input"))
      (node (ref "IC9") (pin "3") (pinfunction "/WP_3") (pintype "input"))
      (node (ref "IC9") (pin "7") (pinfunction "/HOLD_7") (pintype "input"))
      (node (ref "IC9") (pin "8") (pinfunction "VCC_8") (pintype "input"))
      (node (ref "Q2") (pin "3") (pinfunction "D_3") (pintype "passive"))
      (node (ref "Q2") (pin "P2") (pinfunction "D1_P2") (pintype "passive"))
      (node (ref "R18") (pin "1") (pinfunction "1_1") (pintype "passive"))
      (node (ref "R25") (pin "2") (pinfunction "2_2") (pintype "passive"))
      (node (ref "R26") (pin "1") (pinfunction "1_1") (pintype "passive"))
      (node (ref "R27") (pin "1") (pinfunction "1_1") (pintype "passive"))
    )
    (net (code "3") (name "+3.3V{slash}2") (class "Default")
      (node (ref "C41") (pin "1") (pinfunction "1_1") (pintype "passive"))
      (node (ref "C86") (pin "+") (pinfunction "+_+") (pintype "passive"))
      (node (ref "IC12") (pin "8") (pinfunction "VCC_8") (pintype "input"))
      (node (ref "Q1") (pin "3") (pinfunction "D_3") (pintype "passive"))
      (node (ref "Q1") (pin "P2") (pinfunction "D1_P2") (pintype "passive"))
      (node (ref "R30") (pin "2") (pinfunction "2_2") (pintype "passive"))
      (node (ref "R34") (pin "1") (pinfunction "1_1") (pintype "passive"))
      (node (ref "R72") (pin "1") (pinfunction "1_1") (pintype "passive"))
      (node (ref "R73") (pin "2") (pinfunction "2_2") (pintype "passive"))
    )
    (net (code "4") (name "/A+") (class "Default")
      (node (ref "IC14") (pin "3") (pinfunction "3_3") (pintype "passive"))
      (node (ref "J3") (pin "4") (pinfunction "4_4") (pintype "passive"))
      (node (ref "J4") (pin "4") (pinfunction "4_4") (pintype "passive"))
      (node (ref "L8") (pin "2") (pinfunction "2_2") (pintype "passive"))
    )
    (net (code "5") (name "/A++") (class "Default")
      (node (ref "IC12") (pin "6") (pinfunction "A_6") (pintype "bidirectional"))
      (node (ref "L8") (pin "1") (pinfunction "1_1") (pintype "passive"))
      (node (ref "R32") (pin "2") (pinfunction "2_2") (pintype "passive"))
      (node (ref "R34") (pin "2") (pinfunction "2_2") (pintype "passive"))
    )
    (net (code "6") (name "/ACT-L-SENSE") (class "Default")
      (node (ref "R1") (pin "7") (pinfunction "2_7") (pintype "passive"))
      (node (ref "R1") (pin "8") (pinfunction "2_8") (pintype "passive"))
    )
    (net (code "7") (name "/ACT-L-SW") (class "Default")
      (node (ref "C44") (pin "1") (pinfunction "1_1") (pintype "passive"))
      (node (ref "J14") (pin "2") (pinfunction "2_2") (pintype "passive"))
      (node (ref "R1") (pin "1") (pinfunction "1_1") (pintype "passive"))
      (node (ref "R2") (pin "8") (pinfunction "2_8") (pintype "passive"))
    )
    (net (code "8") (name "/ACT-R-SENSE") (class "Default")
      (node (ref "R1") (pin "5") (pinfunction "2_5") (pintype "passive"))
      (node (ref "R1") (pin "6") (pinfunction "2_6") (pintype "passive"))
    )
    (net (code "9") (name "/ACT-R-SW") (class "Default")
      (node (ref "C3") (pin "1") (pinfunction "1_1") (pintype "passive"))
      (node (ref "J15") (pin "2") (pinfunction "2_2") (pintype "passive"))
      (node (ref "R1") (pin "3") (pinfunction "1_3") (pintype "passive"))
      (node (ref "R2") (pin "7") (pinfunction "2_7") (pintype "passive"))
    )
    (net (code "10") (name "/ACT_EN") (class "Default")
      (node (ref "R11") (pin "5") (pinfunction "2_5") (pintype "passive"))
      (node (ref "R11") (pin "6") (pinfunction "2_6") (pintype "passive"))
      (node (ref "R7") (pin "4") (pinfunction "1_4") (pintype "passive"))
    )
    (net (code "11") (name "/ACT_L+") (class "Default")
      (node (ref "IC2") (pin "31") (pinfunction "OUT1A_31") (pintype "output"))
      (node (ref "J14") (pin "1") (pinfunction "1_1") (pintype "passive"))
    )
    (net (code "12") (name "/ACT_L-") (class "Default")
      (node (ref "IC2") (pin "23") (pinfunction "OUT2A_23") (pintype "output"))
      (node (ref "J14") (pin "3") (pinfunction "3_3") (pintype "passive"))
    )
    (net (code "13") (name "/ACT_L1") (class "Default")
      (node (ref "IC2") (pin "27") (pinfunction "IN1_A_27") (pintype "input"))
      (node (ref "R10") (pin "5") (pinfunction "2_5") (pintype "passive"))
    )
    (net (code "14") (name "/ACT_L2") (class "Default")
      (node (ref "IC2") (pin "28") (pinfunction "IN2_A_28") (pintype "input"))
      (node (ref "R10") (pin "6") (pinfunction "2_6") (pintype "passive"))
    )
    (net (code "15") (name "/ACT_R+") (class "Default")
      (node (ref "IC2") (pin "9") (pinfunction "OUT1B_9") (pintype "output"))
      (node (ref "J15") (pin "1") (pinfunction "1_1") (pintype "passive"))
    )
    (net (code "16") (name "/ACT_R-") (class "Default")
      (node (ref "IC2") (pin "19") (pinfunction "OUT2B_19") (pintype "output"))
      (node (ref "J15") (pin "3") (pinfunction "3_3") (pintype "passive"))
    )
    (net (code "17") (name "/ACT_R1") (class "Default")
      (node (ref "IC2") (pin "13") (pinfunction "IN1_B_13") (pintype "input"))
      (node (ref "R10") (pin "7") (pinfunction "2_7") (pintype "passive"))
    )
    (net (code "18") (name "/ACT_R2") (class "Default")
      (node (ref "IC2") (pin "14") (pinfunction "IN2_B_14") (pintype "input"))
      (node (ref "R10") (pin "8") (pinfunction "2_8") (pintype "passive"))
    )
    (net (code "19") (name "/B-") (class "Default")
      (node (ref "IC14") (pin "2") (pinfunction "2_2") (pintype "passive"))
      (node (ref "J3") (pin "5") (pinfunction "5_5") (pintype "passive"))
      (node (ref "J4") (pin "5") (pinfunction "5_5") (pintype "passive"))
      (node (ref "L7") (pin "2") (pinfunction "2_2") (pintype "passive"))
    )
    (net (code "20") (name "/B--") (class "Default")
      (node (ref "IC12") (pin "7") (pinfunction "B_7") (pintype "bidirectional"))
      (node (ref "L7") (pin "1") (pinfunction "1_1") (pintype "passive"))
      (node (ref "R31") (pin "1") (pinfunction "1_1") (pintype "passive"))
      (node (ref "R32") (pin "1") (pinfunction "1_1") (pintype "passive"))
    )
    (net (code "21") (name "/CURR-SENSE") (class "Default")
      (node (ref "C66") (pin "1") (pinfunction "1_1") (pintype "passive"))
      (node (ref "IC1") (pin "14") (pinfunction "AN19/C2INC/RPG9/PMA2/RG9_14") (pintype "bidirectional"))
      (node (ref "O8") (pin "P$1") (pinfunction "TP_P$1") (pintype "passive"))
      (node (ref "R102") (pin "2") (pinfunction "2_2") (pintype "passive"))
      (node (ref "T39") (pin "P$1") (pinfunction "TP_P$1") (pintype "passive"))
    )
    (net (code "22") (name "/D+") (class "Default")
      (node (ref "IC1") (pin "57") (pinfunction "D+/RG2_57") (pintype "bidirectional"))
      (node (ref "IC15") (pin "3") (pinfunction "3_3") (pintype "passive"))
      (node (ref "J12") (pin "3_D+") (pinfunction "D+_3_D+") (pintype "bidirectional"))
    )
    (net (code "23") (name "/D-") (class "Default")
      (node (ref "IC1") (pin "56") (pinfunction "D-/RG3_56") (pintype "bidirectional"))
      (node (ref "IC15") (pin "2") (pinfunction "2_2") (pintype "passive"))
      (node (ref "J12") (pin "2_D-") (pinfunction "D-_2_D-") (pintype "bidirectional"))
    )
    (net (code "24") (name "/DOOR_L") (class "Default")
      (node (ref "R50") (pin "2") (pinfunction "1_2") (pintype "passive"))
      (node (ref "R50") (pin "3") (pinfunction "1_3") (pintype "passive"))
    )
    (net (code "25") (name "/DOOR_L_SW") (class "Default")
      (node (ref "C12") (pin "1") (pinfunction "1_1") (pintype "passive"))
      (node (ref "J14") (pin "4") (pinfunction "4_4") (pintype "passive"))
      (node (ref "R50") (pin "7") (pinfunction "2_7") (pintype "passive"))
      (node (ref "R6") (pin "2") (pinfunction "2_2") (pintype "passive"))
    )
    (net (code "26") (name "/DOOR_ON") (class "Default")
      (node (ref "Q3") (pin "5") (pinfunction "Q1G_5") (pintype "input"))
      (node (ref "R9") (pin "7") (pinfunction "2_7") (pintype "passive"))
    )
    (net (code "27") (name "/DOOR_R") (class "Default")
      (node (ref "R50") (pin "1") (pinfunction "1_1") (pintype "passive"))
      (node (ref "R50") (pin "4") (pinfunction "1_4") (pintype "passive"))
    )
    (net (code "28") (name "/DOOR_R_SW") (class "Default")
      (node (ref "C4") (pin "1") (pinfunction "1_1") (pintype "passive"))
      (node (ref "J15") (pin "4") (pinfunction "4_4") (pintype "passive"))
      (node (ref "R50") (pin "8") (pinfunction "2_8") (pintype "passive"))
      (node (ref "R8") (pin "2") (pinfunction "2_2") (pintype "passive"))
    )
    (net (code "29") (name "/LAN-CTL") (class "Default")
      (node (ref "IC1") (pin "84") (pinfunction "PMD15/RD7_84") (pintype "bidirectional"))
      (node (ref "IC12") (pin "2") (pinfunction "/RE_2") (pintype "input"))
      (node (ref "IC12") (pin "3") (pinfunction "DE_3") (pintype "input"))
      (node (ref "O31") (pin "P$1") (pinfunction "TP_P$1") (pintype "passive"))
      (node (ref "R71") (pin "1") (pinfunction "1_1") (pintype "passive"))
      (node (ref "T15") (pin "P$1") (pinfunction "TP_P$1") (pintype "passive"))
    )
    (net (code "30") (name "/LAN-RX") (class "Default")
      (node (ref "IC1") (pin "88") (pinfunction "RPF1/PMD10/RF1_88") (pintype "bidirectional"))
      (node (ref "IC12") (pin "1") (pinfunction "R_1") (pintype "output"))
      (node (ref "O29") (pin "P$1") (pinfunction "TP_P$1") (pintype "passive"))
      (node (ref "R72") (pin "2") (pinfunction "2_2") (pintype "passive"))
      (node (ref "T13") (pin "P$1") (pinfunction "TP_P$1") (pintype "passive"))
    )
    (net (code "31") (name "/LAN-TX") (class "Default")
      (node (ref "IC1") (pin "87") (pinfunction "RPF0/PMD11/RF0_87") (pintype "bidirectional"))
      (node (ref "IC12") (pin "4") (pinfunction "D_4") (pintype "input"))
      (node (ref "O30") (pin "P$1") (pinfunction "TP_P$1") (pintype "passive"))
      (node (ref "R73") (pin "1") (pinfunction "1_1") (pintype "passive"))
      (node (ref "T14") (pin "P$1") (pinfunction "TP_P$1") (pintype "passive"))
    )
    (net (code "32") (name "/LED-PIC") (class "Default")
      (node (ref "IC1") (pin "1") (pinfunction "RG15_1") (pintype "bidirectional"))
      (node (ref "O1") (pin "P$1") (pinfunction "TP_P$1") (pintype "passive"))
      (node (ref "R29") (pin "1") (pinfunction "1_1") (pintype "passive"))
      (node (ref "T36") (pin "P$1") (pinfunction "TP_P$1") (pintype "passive"))
      (node (ref "TP4") (pin "P$1") (pinfunction "TP_P$1") (pintype "passive"))
    )
    (net (code "33") (name "/PGC") (class "Default")
      (node (ref "IC1") (pin "24") (pinfunction "PGEC1/AN1/RPB1/CTED12/RB1_24") (pintype "bidirectional"))
      (node (ref "J17") (pin "5") (pinfunction "5_5") (pintype "passive"))
    )
    (net (code "34") (name "/PGD") (class "Default")
      (node (ref "IC1") (pin "25") (pinfunction "PGED1/AN0/RPB0/RB0_25") (pintype "bidirectional"))
      (node (ref "J17") (pin "4") (pinfunction "4_4") (pintype "passive"))
      (node (ref "R130") (pin "2") (pinfunction "2_2") (pintype "passive"))
    )
    (net (code "35") (name "/POWER-GOOD") (class "Default")
      (node (ref "IC6") (pin "4") (pinfunction "OUT_4") (pintype "output"))
      (node (ref "R130") (pin "1") (pinfunction "1_1") (pintype "passive"))
      (node (ref "T45") (pin "P$1") (pinfunction "TP_P$1") (pintype "passive"))
      (node (ref "TP2") (pin "P$1") (pinfunction "TP_P$1") (pintype "passive"))
    )
    (net (code "36") (name "/REF-EN") (class "Default")
      (node (ref "IC1") (pin "28") (pinfunction "VREF-/CVREF-/PMA7/RA9_28") (pintype "bidirectional"))
      (node (ref "R93") (pin "1") (pinfunction "1_1") (pintype "passive"))
    )
    (net (code "37") (name "/REF2,5V") (class "Default")
      (node (ref "C57") (pin "1") (pinfunction "1_1") (pintype "passive"))
      (node (ref "IC1") (pin "29") (pinfunction "VREF+/CVREF+/PMA6/RA10_29") (pintype "bidirectional"))
      (node (ref "IC13") (pin "2") (pinfunction "VOUT_2") (pintype "bidirectional"))
    )
    (net (code "38") (name "/SCL1-EEPROM") (class "Default")
      (node (ref "IC1") (pin "66") (pinfunction "SCL1/RPA14/RA14_66") (pintype "bidirectional"))
      (node (ref "IC11") (pin "6") (pinfunction "SCL_6") (pintype "input"))
      (node (ref "IC7") (pin "6") (pinfunction "SCL_6") (pintype "input"))
      (node (ref "R26") (pin "2") (pinfunction "2_2") (pintype "passive"))
    )
    (net (code "39") (name "/SCLK2-SPI") (class "Default")
      (node (ref "IC1") (pin "10") (pinfunction "AN16/C1IND/RPG6/SCK2/PMA5/RG6_10") (pintype "bidirectional"))
      (node (ref "IC9") (pin "6") (pinfunction "C_6") (pintype "input"))
    )
    (net (code "40") (name "/SD-CS") (class "Default")
      (node (ref "IC1") (pin "9") (pinfunction "RPC4/CTED7/RC4_9") (pintype "bidirectional"))
      (node (ref "O5") (pin "P$1") (pinfunction "TP_P$1") (pintype "passive"))
    )
    (net (code "41") (name "/SDA1-EEPROM") (class "Default")
      (node (ref "IC1") (pin "67") (pinfunction "SDA1/RPA15/RA15_67") (pintype "bidirectional"))
      (node (ref "IC11") (pin "5") (pinfunction "SDA_5") (pintype "bidirectional"))
      (node (ref "IC7") (pin "5") (pinfunction "SDA_5") (pintype "bidirectional"))
      (node (ref "R27") (pin "2") (pinfunction "2_2") (pintype "passive"))
    )
    (net (code "42") (name "/SDI2-MISO") (class "Default")
      (node (ref "IC1") (pin "22") (pinfunction "PGED3/AN3/C2INA/RPB3/RB3_22") (pintype "bidirectional"))
      (node (ref "IC9") (pin "2") (pinfunction "Q_2") (pintype "bidirectional"))
      (node (ref "O13") (pin "P$1") (pinfunction "TP_P$1") (pintype "passive"))
    )
    (net (code "43") (name "/SDO2-MOSI") (class "Default")
      (node (ref "IC1") (pin "20") (pinfunction "AN5/C1INA/RPB5/RB5_20") (pintype "bidirectional"))
      (node (ref "IC9") (pin "5") (pinfunction "D_5") (pintype "input"))
      (node (ref "O12") (pin "P$1") (pinfunction "TP_P$1") (pintype "passive"))
    )
    (net (code "44") (name "/VBAT-LAN") (class "Default")
      (node (ref "D3") (pin "C") (pinfunction "C_C") (pintype "passive"))
      (node (ref "J3") (pin "1") (pinfunction "1_1") (pintype "passive"))
      (node (ref "J3") (pin "3") (pinfunction "3_3") (pintype "passive"))
      (node (ref "J4") (pin "1") (pinfunction "1_1") (pintype "passive"))
      (node (ref "J4") (pin "3") (pinfunction "3_3") (pintype "passive"))
      (node (ref "L11") (pin "2") (pinfunction "2_2") (pintype "passive"))
    )
    (net (code "45") (name "/VBAT-LAN-F") (class "Default")
      (node (ref "C33") (pin "1") (pinfunction "1_1") (pintype "passive"))
      (node (ref "C34") (pin "1") (pinfunction "1_1") (pintype "passive"))
      (node (ref "D6") (pin "K") (pinfunction "K_K") (pintype "passive"))
      (node (ref "L11") (pin "1") (pinfunction "1_1") (pintype "passive"))
      (node (ref "Q5") (pin "2") (pinfunction "S_2") (pintype "passive"))
      (node (ref "Q5") (pin "5") (pinfunction "S_5") (pintype "passive"))
      (node (ref "R132") (pin "1") (pinfunction "1_1") (pintype "passive"))
      (node (ref "R36") (pin "2") (pinfunction "2_2") (pintype "passive"))
      (node (ref "R38") (pin "2") (pinfunction "2_2") (pintype "passive"))
      (node (ref "R42") (pin "1") (pinfunction "1_1") (pintype "passive"))
      (node (ref "R45") (pin "1") (pinfunction "1_1") (pintype "passive"))
      (node (ref "R94") (pin "1") (pinfunction "1_1") (pintype "passive"))
    )
    (net (code "46") (name "/VBAT-ON") (class "Default")
      (node (ref "IC1") (pin "52") (pinfunction "RPF2/RF2_52") (pintype "bidirectional"))
      (node (ref "O42") (pin "P$1") (pinfunction "TP_P$1") (pintype "passive"))
      (node (ref "Q4") (pin "2") (pinfunction "G_2") (pintype "passive"))
      (node (ref "R132") (pin "2") (pinfunction "2_2") (pintype "passive"))
      (node (ref "R41") (pin "1") (pinfunction "1_1") (pintype "passive"))
      (node (ref "T5") (pin "P$1") (pinfunction "TP_P$1") (pintype "passive"))
    )
    (net (code "47") (name "/VBAT-SENSE") (class "Default")
      (node (ref "C64") (pin "1") (pinfunction "1_1") (pintype "passive"))
      (node (ref "IC1") (pin "26") (pinfunction "PGEC2/AN6/RPB6/RB6_26") (pintype "bidirectional"))
      (node (ref "O15") (pin "P$1") (pinfunction "TP_P$1") (pintype "passive"))
      (node (ref "R100") (pin "1") (pinfunction "1_1") (pintype "passive"))
      (node (ref "T37") (pin "P$1") (pinfunction "TP_P$1") (pintype "passive"))
    )
    (net (code "48") (name "/VBATLAN-SENSE") (class "Default")
      (node (ref "C36") (pin "1") (pinfunction "1_1") (pintype "passive"))
      (node (ref "IC1") (pin "27") (pinfunction "PGED2/AN7/RPB7/CTED3/RB7_27") (pintype "bidirectional"))
      (node (ref "O16") (pin "P$1") (pinfunction "TP_P$1") (pintype "passive"))
      (node (ref "R101") (pin "1") (pinfunction "1_1") (pintype "passive"))
      (node (ref "T38") (pin "P$1") (pinfunction "TP_P$1") (pintype "passive"))
    )
    (net (code "49") (name "/VBUS") (class "Default")
      (node (ref "IC1") (pin "54") (pinfunction "VBUS_54") (pintype "input"))
      (node (ref "R128") (pin "2") (pinfunction "2_2") (pintype "passive"))
    )
    (net (code "50") (name "/VPS-ON") (class "Default")
      (node (ref "IC1") (pin "53") (pinfunction "RPF8/RF8_53") (pintype "bidirectional"))
      (node (ref "O41") (pin "P$1") (pinfunction "TP_P$1") (pintype "passive"))
      (node (ref "Q4") (pin "5") (pinfunction "G_5") (pintype "passive"))
      (node (ref "R44") (pin "1") (pinfunction "1_1") (pintype "passive"))
      (node (ref "T7") (pin "P$1") (pinfunction "TP_P$1") (pintype "passive"))
    )
    (net (code "51") (name "/VPS-PWR") (class "Default")
      (node (ref "D4") (pin "C") (pinfunction "C_C") (pintype "passive"))
      (node (ref "J3") (pin "6") (pinfunction "6_6") (pintype "passive"))
      (node (ref "J4") (pin "6") (pinfunction "6_6") (pintype "passive"))
      (node (ref "L10") (pin "2") (pinfunction "2_2") (pintype "passive"))
    )
    (net (code "52") (name "/VPS-PWR-F") (class "Default")
      (node (ref "L10") (pin "1") (pinfunction "1_1") (pintype "passive"))
      (node (ref "Q5") (pin "4") (pinfunction "D_4") (pintype "passive"))
      (node (ref "R23") (pin "2") (pinfunction "2_2") (pintype "passive"))
    )
    (net (code "53") (name "/VPS-SENSE") (class "Default")
      (node (ref "C65") (pin "1") (pinfunction "1_1") (pintype "passive"))
      (node (ref "IC1") (pin "12") (pinfunction "AN18/C2IND/RPG8/PMA3/RG8_12") (pintype "bidirectional"))
      (node (ref "O7") (pin "P$1") (pinfunction "TP_P$1") (pintype "passive"))
      (node (ref "R48") (pin "2") (pinfunction "2_2") (pintype "passive"))
      (node (ref "R49") (pin "1") (pinfunction "1_1") (pintype "passive"))
      (node (ref "T3") (pin "P$1") (pinfunction "TP_P$1") (pintype "passive"))
    )
    (net (code "54") (name "/{slash}3.3V1PWRON") (class "Default")
      (node (ref "IC1") (pin "21") (pinfunction "AN4/C1INB/USBOEN/RB4_21") (pintype "bidirectional"))
      (node (ref "O44") (pin "P$1") (pinfunction "TP_P$1") (pintype "passive"))
      (node (ref "R24") (pin "2") (pinfunction "2_2") (pintype "passive"))
      (node (ref "T32") (pin "P$1") (pinfunction "TP_P$1") (pintype "passive"))
    )
    (net (code "55") (name "/{slash}3.3V2PWRON") (class "Default")
      (node (ref "IC1") (pin "96") (pinfunction "TRD1/RG12_96") (pintype "bidirectional"))
      (node (ref "O23") (pin "P$1") (pinfunction "TP_P$1") (pintype "passive"))
      (node (ref "R75") (pin "2") (pinfunction "2_2") (pintype "passive"))
      (node (ref "T33") (pin "P$1") (pinfunction "TP_P$1") (pintype "passive"))
    )
    (net (code "56") (name "/{slash}FMEM1-CS") (class "Default")
      (node (ref "IC1") (pin "11") (pinfunction "AN17/C1INC/RPG7/PMA4/RG7_11") (pintype "bidirectional"))
      (node (ref "IC9") (pin "1") (pinfunction "/S_1") (pintype "input"))
      (node (ref "O6") (pin "P$1") (pinfunction "TP_P$1") (pintype "passive"))
      (node (ref "R25") (pin "1") (pinfunction "1_1") (pintype "passive"))
      (node (ref "T27") (pin "P$1") (pinfunction "TP_P$1") (pintype "passive"))
    )
    (net (code "57") (name "/{slash}MCLR") (class "Default")
      (node (ref "IC1") (pin "13") (pinfunction "~{MCLR}_13") (pintype "input"))
      (node (ref "J17") (pin "1") (pinfunction "1_1") (pintype "passive"))
      (node (ref "R90") (pin "2") (pinfunction "2_2") (pintype "passive"))
    )
    (net (code "58") (name "DGND") (class "Default")
      (node (ref "C22") (pin "2") (pinfunction "2_2") (pintype "passive"))
      (node (ref "C23") (pin "2") (pinfunction "2_2") (pintype "passive"))
      (node (ref "C24") (pin "1") (pinfunction "1_1") (pintype "passive"))
      (node (ref "C27") (pin "2") (pinfunction "2_2") (pintype "passive"))
      (node (ref "C28") (pin "2") (pinfunction "2_2") (pintype "passive"))
      (node (ref "C29") (pin "2") (pinfunction "2_2") (pintype "passive"))
      (node (ref "C30") (pin "2") (pinfunction "2_2") (pintype "passive"))
      (node (ref "C31") (pin "-") (pinfunction "-_-") (pintype "passive"))
      (node (ref "C35") (pin "2") (pinfunction "2_2") (pintype "passive"))
      (node (ref "C36") (pin "2") (pinfunction "2_2") (pintype "passive"))
      (node (ref "C40") (pin "2") (pinfunction "2_2") (pintype "passive"))
      (node (ref "C41") (pin "2") (pinfunction "2_2") (pintype "passive"))
      (node (ref "C47") (pin "2") (pinfunction "2_2") (pintype "passive"))
      (node (ref "C48") (pin "2") (pinfunction "2_2") (pintype "passive"))
      (node (ref "C49") (pin "2") (pinfunction "2_2") (pintype "passive"))
      (node (ref "C50") (pin "2") (pinfunction "2_2") (pintype "passive"))
      (node (ref "C51") (pin "2") (pinfunction "2_2") (pintype "passive"))
      (node (ref "C52") (pin "2") (pinfunction "2_2") (pintype "passive"))
      (node (ref "C53") (pin "2") (pinfunction "2_2") (pintype "passive"))
      (node (ref "C54") (pin "-") (pinfunction "-_-") (pintype "passive"))
      (node (ref "C55") (pin "2") (pinfunction "2_2") (pintype "passive"))
      (node (ref "C56") (pin "-") (pinfunction "-_-") (pintype "passive"))
      (node (ref "C57") (pin "2") (pinfunction "2_2") (pintype "passive"))
      (node (ref "C58") (pin "2") (pinfunction "2_2") (pintype "passive"))
      (node (ref "C59") (pin "2") (pinfunction "2_2") (pintype "passive"))
      (node (ref "C60") (pin "2") (pinfunction "2_2") (pintype "passive"))
      (node (ref "C61") (pin "2") (pinfunction "2_2") (pintype "passive"))
      (node (ref "C62") (pin "2") (pinfunction "2_2") (pintype "passive"))
      (node (ref "C63") (pin "2") (pinfunction "2_2") (pintype "passive"))
      (node (ref "C64") (pin "2") (pinfunction "2_2") (pintype "passive"))
      (node (ref "C65") (pin "2") (pinfunction "2_2") (pintype "passive"))
      (node (ref "C66") (pin "2") (pinfunction "2_2") (pintype "passive"))
      (node (ref "C67") (pin "2") (pinfunction "2_2") (pintype "passive"))
      (node (ref "C81") (pin "-") (pinfunction "-_-") (pintype "passive"))
      (node (ref "C83") (pin "2") (pinfunction "2_2") (pintype "passive"))
      (node (ref "C84") (pin "2") (pinfunction "2_2") (pintype "passive"))
      (node (ref "C85") (pin "2") (pinfunction "2_2") (pintype "passive"))
      (node (ref "C86") (pin "-") (pinfunction "-_-") (pintype "passive"))
      (node (ref "C88") (pin "2") (pinfunction "2_2") (pintype "passive"))
      (node (ref "D2") (pin "-") (pinfunction "A_-") (pintype "passive"))
      (node (ref "D5") (pin "K") (pinfunction "K_K") (pintype "passive"))
      (node (ref "D7") (pin "A") (pinfunction "A_A") (pintype "passive"))
      (node (ref "IC1") (pin "15") (pinfunction "VSS2_15") (pintype "input"))
      (node (ref "IC1") (pin "31") (pinfunction "AVSS_31") (pintype "input"))
      (node (ref "IC1") (pin "36") (pinfunction "VSS3_36") (pintype "input"))
      (node (ref "IC1") (pin "45") (pinfunction "VSS4_45") (pintype "input"))
      (node (ref "IC1") (pin "65") (pinfunction "VSS5_65") (pintype "input"))
      (node (ref "IC1") (pin "75") (pinfunction "VSS1_75") (pintype "input"))
      (node (ref "IC10") (pin "1") (pinfunction "GND_1") (pintype "input"))
      (node (ref "IC10") (pin "2") (pinfunction "GND1_2") (pintype "input"))
      (node (ref "IC11") (pin "1") (pinfunction "A0_1") (pintype "input"))
      (node (ref "IC11") (pin "3") (pinfunction "A2_3") (pintype "input"))
      (node (ref "IC11") (pin "4") (pinfunction "GND_4") (pintype "input"))
      (node (ref "IC12") (pin "5") (pinfunction "GND_5") (pintype "input"))
      (node (ref "IC13") (pin "3") (pinfunction "GND_3") (pintype "bidirectional"))
      (node (ref "IC15") (pin "1") (pinfunction "1_1") (pintype "input"))
      (node (ref "IC16") (pin "4") (pinfunction "V-_4") (pintype "input"))
      (node (ref "IC6") (pin "2") (pinfunction "GND_2") (pintype "input"))
      (node (ref "IC7") (pin "1") (pinfunction "A0_1") (pintype "input"))
      (node (ref "IC7") (pin "2") (pinfunction "A1_2") (pintype "input"))
      (node (ref "IC7") (pin "3") (pinfunction "A2_3") (pintype "input"))
      (node (ref "IC7") (pin "4") (pinfunction "GND_4") (pintype "input"))
      (node (ref "IC7") (pin "7") (pinfunction "WP_7") (pintype "input"))
      (node (ref "IC8") (pin "10") (pinfunction "SYNC_10") (pintype "bidirectional"))
      (node (ref "IC8") (pin "EP") (pinfunction "GND_EP") (pintype "bidirectional"))
      (node (ref "IC9") (pin "4") (pinfunction "GND_4") (pintype "input"))
      (node (ref "J12") (pin "4_GND") (pinfunction "GND_4_GND") (pintype "bidirectional"))
      (node (ref "J12") (pin "SH1") (pinfunction "GND_SH1_SH1") (pintype "bidirectional"))
      (node (ref "J12") (pin "SH2") (pinfunction "GND_SH2_SH2") (pintype "bidirectional"))
      (node (ref "J17") (pin "3") (pinfunction "3_3") (pintype "passive"))
      (node (ref "L12") (pin "1") (pinfunction "1_1") (pintype "passive"))
      (node (ref "L2") (pin "2") (pinfunction "2_2") (pintype "passive"))
      (node (ref "PCB1") (pin "PAD_GND_1") (pinfunction "PAD_GND_1_PAD_GND_1") (pintype "bidirectional"))
      (node (ref "PCB1") (pin "PAD_GND_2") (pinfunction "PAD_GND_2_PAD_GND_2") (pintype "bidirectional"))
      (node (ref "PCB1") (pin "PAD_GND_3") (pinfunction "PAD_GND_3_PAD_GND_3") (pintype "bidirectional"))
      (node (ref "PCB1") (pin "PAD_GND_4") (pinfunction "PAD_GND_4_PAD_GND_4") (pintype "bidirectional"))
      (node (ref "R17") (pin "2") (pinfunction "2_2") (pintype "passive"))
      (node (ref "R19") (pin "2") (pinfunction "2_2") (pintype "passive"))
      (node (ref "R21") (pin "2") (pinfunction "2_2") (pintype "passive"))
      (node (ref "R31") (pin "2") (pinfunction "2_2") (pintype "passive"))
      (node (ref "R40") (pin "1") (pinfunction "1_1") (pintype "passive"))
      (node (ref "R41") (pin "2") (pinfunction "2_2") (pintype "passive"))
      (node (ref "R43") (pin "1") (pinfunction "1_1") (pintype "passive"))
      (node (ref "R44") (pin "2") (pinfunction "2_2") (pintype "passive"))
      (node (ref "R46") (pin "1") (pinfunction "1_1") (pintype "passive"))
      (node (ref "R48") (pin "1") (pinfunction "1_1") (pintype "passive"))
      (node (ref "R71") (pin "2") (pinfunction "2_2") (pintype "passive"))
      (node (ref "R96") (pin "2") (pinfunction "2_2") (pintype "passive"))
      (node (ref "R99") (pin "2") (pinfunction "2_2") (pintype "passive"))
    )
    (net (code "59") (name "Net-(C24-Pad2)") (class "Default")
      (node (ref "C24") (pin "2") (pinfunction "2_2") (pintype "passive"))
      (node (ref "R77") (pin "2") (pinfunction "2_2") (pintype "passive"))
    )
    (net (code "60") (name "Net-(C39-Pad1)") (class "Default")
      (node (ref "C39") (pin "1") (pinfunction "1_1") (pintype "passive"))
      (node (ref "IC14") (pin "4") (pinfunction "4_4") (pintype "input"))
      (node (ref "R30") (pin "1") (pinfunction "1_1") (pintype "passive"))
    )
    (net (code "61") (name "Net-(C39-Pad2)") (class "Default")
      (node (ref "C39") (pin "2") (pinfunction "2_2") (pintype "passive"))
      (node (ref "D3") (pin "A") (pinfunction "A_A") (pintype "passive"))
      (node (ref "D4") (pin "A") (pinfunction "A_A") (pintype "passive"))
      (node (ref "IC14") (pin "1") (pinfunction "1_1") (pintype "input"))
      (node (ref "J3") (pin "2") (pinfunction "2_2") (pintype "passive"))
      (node (ref "J3") (pin "7") (pinfunction "7_7") (pintype "passive"))
      (node (ref "J3") (pin "8") (pinfunction "8_8") (pintype "passive"))
      (node (ref "J4") (pin "2") (pinfunction "2_2") (pintype "passive"))
      (node (ref "J4") (pin "7") (pinfunction "7_7") (pintype "passive"))
      (node (ref "J4") (pin "8") (pinfunction "8_8") (pintype "passive"))
      (node (ref "L12") (pin "2") (pinfunction "2_2") (pintype "passive"))
    )
    (net (code "62") (name "Net-(C40-Pad1)") (class "Default")
      (node (ref "C40") (pin "1") (pinfunction "1_1") (pintype "passive"))
      (node (ref "R90") (pin "1") (pinfunction "1_1") (pintype "passive"))
      (node (ref "R91") (pin "1") (pinfunction "1_1") (pintype "passive"))
    )
    (net (code "63") (name "Net-(D1-K)") (class "Default")
      (node (ref "C37") (pin "2") (pinfunction "2_2") (pintype "passive"))
      (node (ref "D1") (pin "2") (pinfunction "K_2") (pintype "passive"))
      (node (ref "IC2") (pin "17") (pinfunction "VBOOT_17") (pintype "input"))
    )
    (net (code "64") (name "Net-(D1-KA)") (class "Default")
      (node (ref "C2") (pin "1") (pinfunction "1_1") (pintype "passive"))
      (node (ref "D1") (pin "3") (pinfunction "KA_3") (pintype "passive"))
    )
    (net (code "65") (name "Net-(D2-C)") (class "Default")
      (node (ref "C26") (pin "1") (pinfunction "1_1") (pintype "passive"))
      (node (ref "C30") (pin "1") (pinfunction "1_1") (pintype "passive"))
      (node (ref "C31") (pin "+") (pinfunction "+_+") (pintype "passive"))
      (node (ref "D2") (pin "+") (pinfunction "C_+") (pintype "passive"))
      (node (ref "IC8") (pin "1") (pinfunction "BD_1") (pintype "bidirectional"))
      (node (ref "L9") (pin "2") (pinfunction "2_2") (pintype "passive"))
      (node (ref "R129") (pin "2") (pinfunction "2_2") (pintype "passive"))
      (node (ref "R20") (pin "1") (pinfunction "1_1") (pintype "passive"))
    )
    (net (code "66") (name "Net-(D5-PadA)") (class "Default")
      (node (ref "D5") (pin "A") (pinfunction "A_A") (pintype "passive"))
      (node (ref "R29") (pin "2") (pinfunction "2_2") (pintype "passive"))
    )
    (net (code "67") (name "Net-(D9-C)") (class "Default")
      (node (ref "D9") (pin "3") (pinfunction "C_3") (pintype "passive"))
      (node (ref "R2") (pin "1") (pinfunction "1_1") (pintype "passive"))
      (node (ref "R2") (pin "2") (pinfunction "1_2") (pintype "passive"))
      (node (ref "R7") (pin "6") (pinfunction "2_6") (pintype "passive"))
    )
    (net (code "68") (name "Net-(IC1-AVDD)") (class "Default")
      (node (ref "C55") (pin "1") (pinfunction "1_1") (pintype "passive"))
      (node (ref "C56") (pin "+") (pinfunction "+_+") (pintype "passive"))
      (node (ref "C88") (pin "1") (pinfunction "1_1") (pintype "passive"))
      (node (ref "IC1") (pin "30") (pinfunction "AVDD_30") (pintype "input"))
      (node (ref "R92") (pin "2") (pinfunction "2_2") (pintype "passive"))
    )
    (net (code "69") (name "Net-(IC1-CLKI{slash}RC12{slash}OSC1)") (class "Default")
      (node (ref "C60") (pin "1") (pinfunction "1_1") (pintype "passive"))
      (node (ref "IC1") (pin "63") (pinfunction "CLKI/RC12/OSC1_63") (pintype "bidirectional"))
      (node (ref "X1") (pin "3") (pinfunction "2_3") (pintype "passive"))
    )
    (net (code "70") (name "Net-(IC1-CLKO{slash}RC15{slash}OSC2)") (class "Default")
      (node (ref "C61") (pin "1") (pinfunction "1_1") (pintype "passive"))
      (node (ref "IC1") (pin "64") (pinfunction "CLKO/RC15/OSC2_64") (pintype "bidirectional"))
      (node (ref "X1") (pin "1") (pinfunction "1_1") (pintype "passive"))
    )
    (net (code "71") (name "Net-(IC1-VCAP)") (class "Default")
      (node (ref "C53") (pin "1") (pinfunction "1_1") (pintype "passive"))
      (node (ref "C54") (pin "+") (pinfunction "+_+") (pintype "passive"))
      (node (ref "IC1") (pin "85") (pinfunction "VCAP_85") (pintype "input"))
    )
    (net (code "72") (name "Net-(IC2-EN_A)") (class "Default")
      (node (ref "C5") (pin "1") (pinfunction "1_1") (pintype "passive"))
      (node (ref "IC2") (pin "25") (pinfunction "EN_A_25") (pintype "input"))
      (node (ref "R11") (pin "4") (pinfunction "1_4") (pintype "passive"))
    )
    (net (code "73") (name "Net-(IC2-EN_B)") (class "Default")
      (node (ref "C43") (pin "1") (pinfunction "1_1") (pintype "passive"))
      (node (ref "IC2") (pin "16") (pinfunction "EN_B_16") (pintype "input"))
      (node (ref "R11") (pin "3") (pinfunction "1_3") (pintype "passive"))
    )
    (net (code "74") (name "Net-(IC2-RCA)") (class "Default")
      (node (ref "C7") (pin "1") (pinfunction "1_1") (pintype "passive"))
      (node (ref "IC2") (pin "30") (pinfunction "RCA_30") (pintype "input"))
      (node (ref "R11") (pin "2") (pinfunction "1_2") (pintype "passive"))
    )
    (net (code "75") (name "Net-(IC2-RCB)") (class "Default")
      (node (ref "C6") (pin "1") (pinfunction "1_1") (pintype "passive"))
      (node (ref "IC2") (pin "11") (pinfunction "RCB_11") (pintype "input"))
      (node (ref "R11") (pin "1") (pinfunction "1_1") (pintype "passive"))
    )
    (net (code "76") (name "Net-(IC2-SENSE_A)") (class "Default")
      (node (ref "IC2") (pin "29") (pinfunction "SENSE_A_29") (pintype "input"))
      (node (ref "R5") (pin "2") (pinfunction "2_2") (pintype "passive"))
    )
    (net (code "77") (name "Net-(IC2-SENSE_B)") (class "Default")
      (node (ref "IC2") (pin "12") (pinfunction "SENSE_B_12") (pintype "input"))
      (node (ref "R4") (pin "2") (pinfunction "2_2") (pintype "passive"))
    )
    (net (code "78") (name "Net-(IC2-VCP)") (class "Default")
      (node (ref "C2") (pin "2") (pinfunction "2_2") (pintype "passive"))
      (node (ref "IC2") (pin "24") (pinfunction "VCP_24") (pintype "input"))
    )
    (net (code "79") (name "Net-(IC2-VREF_A)") (class "Default")
      (node (ref "IC2") (pin "15") (pinfunction "VREF_B_15") (pintype "input"))
      (node (ref "IC2") (pin "26") (pinfunction "VREF_A_26") (pintype "input"))
      (node (ref "R3") (pin "2") (pinfunction "2_2") (pintype "passive"))
      (node (ref "R7") (pin "5") (pinfunction "2_5") (pintype "passive"))
    )
    (net (code "80") (name "Net-(IC6-HTH)") (class "Default")
      (node (ref "IC6") (pin "1") (pinfunction "HTH_1") (pintype "input"))
      (node (ref "R46") (pin "2") (pinfunction "2_2") (pintype "passive"))
      (node (ref "R47") (pin "1") (pinfunction "1_1") (pintype "passive"))
    )
    (net (code "81") (name "Net-(IC6-LTH)") (class "Default")
      (node (ref "IC6") (pin "3") (pinfunction "LTH_3") (pintype "input"))
      (node (ref "R33") (pin "1") (pinfunction "1_1") (pintype "passive"))
      (node (ref "R47") (pin "2") (pinfunction "2_2") (pintype "passive"))
    )
    (net (code "82") (name "Net-(IC6-VDD)") (class "Default")
      (node (ref "C35") (pin "1") (pinfunction "1_1") (pintype "passive"))
      (node (ref "IC6") (pin "5") (pinfunction "VDD_5") (pintype "input"))
      (node (ref "R28") (pin "1") (pinfunction "1_1") (pintype "passive"))
    )
    (net (code "83") (name "Net-(IC8-BOOST)") (class "Default")
      (node (ref "C25") (pin "2") (pinfunction "2_2") (pintype "passive"))
      (node (ref "IC8") (pin "2") (pinfunction "BOOST_2") (pintype "bidirectional"))
    )
    (net (code "84") (name "Net-(IC8-EN)") (class "Default")
      (node (ref "IC8") (pin "5") (pinfunction "EN_5") (pintype "bidirectional"))
      (node (ref "JP1") (pin "2") (pinfunction "2_2") (pintype "bidirectional"))
      (node (ref "R22") (pin "2") (pinfunction "2_2") (pintype "passive"))
    )
    (net (code "85") (name "Net-(IC8-FB)") (class "Default")
      (node (ref "C26") (pin "2") (pinfunction "2_2") (pintype "passive"))
      (node (ref "IC8") (pin "6") (pinfunction "FB_6") (pintype "bidirectional"))
      (node (ref "R19") (pin "1") (pinfunction "1_1") (pintype "passive"))
      (node (ref "R20") (pin "2") (pinfunction "2_2") (pintype "passive"))
    )
    (net (code "86") (name "Net-(IC8-RT)") (class "Default")
      (node (ref "IC8") (pin "8") (pinfunction "RT_8") (pintype "bidirectional"))
      (node (ref "R17") (pin "1") (pinfunction "1_1") (pintype "passive"))
    )
    (net (code "87") (name "Net-(IC8-SS)") (class "Default")
      (node (ref "IC8") (pin "7") (pinfunction "SS_7") (pintype "bidirectional"))
      (node (ref "R77") (pin "1") (pinfunction "1_1") (pintype "passive"))
    )
    (net (code "88") (name "Net-(IC8-SW)") (class "Default")
      (node (ref "C25") (pin "1") (pinfunction "1_1") (pintype "passive"))
      (node (ref "D7") (pin "K") (pinfunction "K_K") (pintype "passive"))
      (node (ref "IC8") (pin "3") (pinfunction "SW_3") (pintype "bidirectional"))
      (node (ref "L9") (pin "1") (pinfunction "1_1") (pintype "passive"))
    )
    (net (code "89") (name "Net-(IC10-OUT)") (class "Default")
      (node (ref "IC10") (pin "3") (pinfunction "OUT_3") (pintype "output"))
      (node (ref "R102") (pin "1") (pinfunction "1_1") (pintype "passive"))
    )
    (net (code "90") (name "Net-(IC10-VIN+)") (class "Default")
      (node (ref "C29") (pin "1") (pinfunction "1_1") (pintype "passive"))
      (node (ref "F1") (pin "1") (pinfunction "1_1") (pintype "passive"))
      (node (ref "IC10") (pin "5") (pinfunction "VIN+_5") (pintype "input"))
      (node (ref "R39") (pin "2") (pinfunction "2_2") (pintype "passive"))
    )
    (net (code "91") (name "Net-(IC11-WP)") (class "Default")
      (node (ref "IC11") (pin "7") (pinfunction "WP_7") (pintype "input"))
      (node (ref "R18") (pin "2") (pinfunction "2_2") (pintype "passive"))
      (node (ref "TP1") (pin "P$1") (pinfunction "TP_P$1") (pintype "passive"))
    )
    (net (code "92") (name "Net-(IC13-VIN)") (class "Default")
      (node (ref "C58") (pin "1") (pinfunction "1_1") (pintype "passive"))
      (node (ref "C59") (pin "1") (pinfunction "1_1") (pintype "passive"))
      (node (ref "IC13") (pin "1") (pinfunction "VIN_1") (pintype "bidirectional"))
      (node (ref "R93") (pin "2") (pinfunction "2_2") (pintype "passive"))
    )
    (net (code "93") (name "Net-(IC16A-+IN)") (class "Default")
      (node (ref "C62") (pin "1") (pinfunction "1_1") (pintype "passive"))
      (node (ref "IC16") (pin "3") (pinfunction "+IN_3") (pintype "input"))
      (node (ref "R95") (pin "2") (pinfunction "2_2") (pintype "passive"))
      (node (ref "R96") (pin "1") (pinfunction "1_1") (pintype "passive"))
    )
    (net (code "94") (name "Net-(IC16A--IN)") (class "Default")
      (node (ref "IC16") (pin "1") (pinfunction "OUT_1") (pintype "output"))
      (node (ref "IC16") (pin "2") (pinfunction "-IN_2") (pintype "input"))
      (node (ref "R101") (pin "2") (pinfunction "2_2") (pintype "passive"))
    )
    (net (code "95") (name "Net-(IC16B-+IN)") (class "Default")
      (node (ref "C63") (pin "1") (pinfunction "1_1") (pintype "passive"))
      (node (ref "IC16") (pin "5") (pinfunction "+IN_5") (pintype "input"))
      (node (ref "R98") (pin "2") (pinfunction "2_2") (pintype "passive"))
      (node (ref "R99") (pin "1") (pinfunction "1_1") (pintype "passive"))
    )
    (net (code "96") (name "Net-(IC16B--IN)") (class "Default")
      (node (ref "IC16") (pin "6") (pinfunction "-IN_6") (pintype "input"))
      (node (ref "IC16") (pin "7") (pinfunction "OUT_7") (pintype "output"))
      (node (ref "R100") (pin "2") (pinfunction "2_2") (pintype "passive"))
    )
    (net (code "97") (name "Net-(IC16C-V+)") (class "Default")
      (node (ref "C67") (pin "1") (pinfunction "1_1") (pintype "passive"))
      (node (ref "IC16") (pin "8") (pinfunction "V+_8") (pintype "input"))
      (node (ref "R103") (pin "1") (pinfunction "1_1") (pintype "passive"))
    )
    (net (code "98") (name "Net-(J12-+5V)") (class "Default")
      (node (ref "C85") (pin "1") (pinfunction "1_1") (pintype "passive"))
      (node (ref "D6") (pin "A") (pinfunction "A_A") (pintype "passive"))
      (node (ref "IC15") (pin "4") (pinfunction "4_4") (pintype "input"))
      (node (ref "J12") (pin "1_+5V") (pinfunction "+5V_1_+5V") (pintype "bidirectional"))
      (node (ref "R128") (pin "1") (pinfunction "1_1") (pintype "passive"))
    )
    (net (code "99") (name "Net-(JP1-Pad1)") (class "Default")
      (node (ref "JP1") (pin "1") (pinfunction "1_1") (pintype "bidirectional"))
      (node (ref "R21") (pin "1") (pinfunction "1_1") (pintype "passive"))
    )
    (net (code "100") (name "Net-(L13-Pad2)") (class "Default")
      (node (ref "L13") (pin "2") (pinfunction "2_2") (pintype "passive"))
      (node (ref "R92") (pin "1") (pinfunction "1_1") (pintype "passive"))
    )
    (net (code "101") (name "Net-(Q1B-G)") (class "Default")
      (node (ref "C70") (pin "2") (pinfunction "2_2") (pintype "passive"))
      (node (ref "Q1") (pin "5") (pinfunction "G_5") (pintype "passive"))
      (node (ref "R75") (pin "1") (pinfunction "1_1") (pintype "passive"))
      (node (ref "R82") (pin "2") (pinfunction "2_2") (pintype "passive"))
    )
    (net (code "102") (name "Net-(Q1B-S)") (class "Default")
      (node (ref "Q1") (pin "4") (pinfunction "S_4") (pintype "passive"))
      (node (ref "R106") (pin "1") (pinfunction "1_1") (pintype "passive"))
    )
    (net (code "103") (name "Net-(Q2B-G)") (class "Default")
      (node (ref "C69") (pin "2") (pinfunction "2_2") (pintype "passive"))
      (node (ref "Q2") (pin "5") (pinfunction "G_5") (pintype "passive"))
      (node (ref "R24") (pin "1") (pinfunction "1_1") (pintype "passive"))
      (node (ref "R65") (pin "2") (pinfunction "2_2") (pintype "passive"))
    )
    (net (code "104") (name "Net-(Q2B-S)") (class "Default")
      (node (ref "Q2") (pin "4") (pinfunction "S_4") (pintype "passive"))
      (node (ref "R105") (pin "1") (pinfunction "1_1") (pintype "passive"))
    )
    (net (code "105") (name "Net-(Q3-Q2D1)") (class "Default")
      (node (ref "Q3") (pin "2") (pinfunction "Q2D1_2") (pintype "bidirectional"))
      (node (ref "Q3") (pin "3") (pinfunction "Q2D2_3") (pintype "bidirectional"))
      (node (ref "R6") (pin "1") (pinfunction "1_1") (pintype "passive"))
      (node (ref "R8") (pin "1") (pinfunction "1_1") (pintype "passive"))
    )
    (net (code "106") (name "Net-(Q3-Q2G)") (class "Default")
      (node (ref "Q3") (pin "6") (pinfunction "Q2G_6") (pintype "input"))
      (node (ref "R9") (pin "3") (pinfunction "1_3") (pintype "passive"))
    )
    (net (code "107") (name "Net-(Q4A-D)") (class "Default")
      (node (ref "C33") (pin "2") (pinfunction "2_2") (pintype "passive"))
      (node (ref "Q4") (pin "6") (pinfunction "D_6") (pintype "passive"))
      (node (ref "Q5") (pin "1") (pinfunction "G_1") (pintype "passive"))
      (node (ref "R42") (pin "2") (pinfunction "2_2") (pintype "passive"))
    )
    (net (code "108") (name "Net-(Q4A-S)") (class "Default")
      (node (ref "Q4") (pin "1") (pinfunction "S_1") (pintype "passive"))
      (node (ref "R40") (pin "2") (pinfunction "2_2") (pintype "passive"))
    )
    (net (code "109") (name "Net-(Q4B-D)") (class "Default")
      (node (ref "C34") (pin "2") (pinfunction "2_2") (pintype "passive"))
      (node (ref "Q4") (pin "3") (pinfunction "D_3") (pintype "passive"))
      (node (ref "Q5") (pin "3") (pinfunction "G_3") (pintype "passive"))
      (node (ref "R45") (pin "2") (pinfunction "2_2") (pintype "passive"))
    )
    (net (code "110") (name "Net-(Q4B-S)") (class "Default")
      (node (ref "Q4") (pin "4") (pinfunction "S_4") (pintype "passive"))
      (node (ref "R43") (pin "2") (pinfunction "2_2") (pintype "passive"))
    )
    (net (code "111") (name "Net-(Q5A-D)") (class "Default")
      (node (ref "F1") (pin "2") (pinfunction "2_2") (pintype "passive"))
      (node (ref "Q5") (pin "6") (pinfunction "D_6") (pintype "passive"))
      (node (ref "R35") (pin "1") (pinfunction "1_1") (pintype "passive"))
      (node (ref "R37") (pin "1") (pinfunction "1_1") (pintype "passive"))
      (node (ref "R97") (pin "1") (pinfunction "1_1") (pintype "passive"))
    )
    (net (code "112") (name "Net-(R23-Pad1)") (class "Default")
      (node (ref "R23") (pin "1") (pinfunction "1_1") (pintype "passive"))
      (node (ref "R49") (pin "2") (pinfunction "2_2") (pintype "passive"))
    )
    (net (code "113") (name "Net-(R35-Pad2)") (class "Default")
      (node (ref "R35") (pin "2") (pinfunction "2_2") (pintype "passive"))
      (node (ref "R36") (pin "1") (pinfunction "1_1") (pintype "passive"))
      (node (ref "R37") (pin "2") (pinfunction "2_2") (pintype "passive"))
      (node (ref "R38") (pin "1") (pinfunction "1_1") (pintype "passive"))
    )
    (net (code "114") (name "Net-(R94-Pad2)") (class "Default")
      (node (ref "R94") (pin "2") (pinfunction "2_2") (pintype "passive"))
      (node (ref "R95") (pin "1") (pinfunction "1_1") (pintype "passive"))
    )
    (net (code "115") (name "Net-(R97-Pad2)") (class "Default")
      (node (ref "R97") (pin "2") (pinfunction "2_2") (pintype "passive"))
      (node (ref "R98") (pin "1") (pinfunction "1_1") (pintype "passive"))
    )
    (net (code "116") (name "PGND") (class "Default")
      (node (ref "C1") (pin "2") (pinfunction "2_2") (pintype "passive"))
      (node (ref "C12") (pin "2") (pinfunction "2_2") (pintype "passive"))
      (node (ref "C3") (pin "2") (pinfunction "2_2") (pintype "passive"))
      (node (ref "C38") (pin "2") (pinfunction "2_2") (pintype "passive"))
      (node (ref "C4") (pin "2") (pinfunction "2_2") (pintype "passive"))
      (node (ref "C43") (pin "2") (pinfunction "2_2") (pintype "passive"))
      (node (ref "C44") (pin "2") (pinfunction "2_2") (pintype "passive"))
      (node (ref "C5") (pin "2") (pinfunction "2_2") (pintype "passive"))
      (node (ref "C6") (pin "2") (pinfunction "2_2") (pintype "passive"))
      (node (ref "C7") (pin "2") (pinfunction "2_2") (pintype "passive"))
      (node (ref "D8") (pin "A") (pinfunction "A_A") (pintype "passive"))
      (node (ref "D9") (pin "1") (pinfunction "A_1") (pintype "passive"))
      (node (ref "IC2") (pin "1") (pinfunction "GND1_1") (pintype "input"))
      (node (ref "IC2") (pin "2") (pinfunction "GND2_2") (pintype "input"))
      (node (ref "IC2") (pin "21") (pinfunction "GND21_21") (pintype "input"))
      (node (ref "IC2") (pin "3") (pinfunction "GND3_3") (pintype "input"))
      (node (ref "IC2") (pin "4") (pinfunction "GND4_4") (pintype "input"))
      (node (ref "IC2") (pin "5") (pinfunction "GND5_5") (pintype "input"))
      (node (ref "IC2") (pin "6") (pinfunction "GND6_6") (pintype "input"))
      (node (ref "IC2") (pin "7") (pinfunction "GND7_7") (pintype "input"))
      (node (ref "IC2") (pin "8") (pinfunction "GND8_8") (pintype "input"))
      (node (ref "IC2") (pin "G") (pinfunction "GNEXP_G") (pintype "input"))
      (node (ref "J14") (pin "5") (pinfunction "5_5") (pintype "passive"))
      (node (ref "J15") (pin "5") (pinfunction "5_5") (pintype "passive"))
      (node (ref "L2") (pin "1") (pinfunction "1_1") (pintype "passive"))
      (node (ref "Q3") (pin "1") (pinfunction "Q1S_1") (pintype "bidirectional"))
      (node (ref "R1") (pin "2") (pinfunction "1_2") (pintype "passive"))
      (node (ref "R1") (pin "4") (pinfunction "1_4") (pintype "passive"))
      (node (ref "R10") (pin "1") (pinfunction "1_1") (pintype "passive"))
      (node (ref "R10") (pin "2") (pinfunction "1_2") (pintype "passive"))
      (node (ref "R10") (pin "3") (pinfunction "1_3") (pintype "passive"))
      (node (ref "R10") (pin "4") (pinfunction "1_4") (pintype "passive"))
      (node (ref "R11") (pin "7") (pinfunction "2_7") (pintype "passive"))
      (node (ref "R11") (pin "8") (pinfunction "2_8") (pintype "passive"))
      (node (ref "R3") (pin "1") (pinfunction "1_1") (pintype "passive"))
      (node (ref "R4") (pin "1") (pinfunction "1_1") (pintype "passive"))
      (node (ref "R5") (pin "1") (pinfunction "1_1") (pintype "passive"))
      (node (ref "R50") (pin "5") (pinfunction "2_5") (pintype "passive"))
      (node (ref "R50") (pin "6") (pinfunction "2_6") (pintype "passive"))
      (node (ref "R9") (pin "2") (pinfunction "1_2") (pintype "passive"))
    )
    (net (code "117") (name "VACT") (class "Default")
      (node (ref "C1") (pin "1") (pinfunction "1_1") (pintype "passive"))
      (node (ref "C37") (pin "1") (pinfunction "1_1") (pintype "passive"))
      (node (ref "C38") (pin "1") (pinfunction "1_1") (pintype "passive"))
      (node (ref "D1") (pin "1") (pinfunction "A_1") (pintype "passive"))
      (node (ref "D8") (pin "C") (pinfunction "C_C") (pintype "passive"))
      (node (ref "IC2") (pin "20") (pinfunction "VS_B_20") (pintype "input"))
      (node (ref "IC2") (pin "22") (pinfunction "VS_A_22") (pintype "input"))
      (node (ref "R7") (pin "3") (pinfunction "1_3") (pintype "passive"))
    )
    (net (code "118") (name "VBAT") (class "Default")
      (node (ref "C22") (pin "1") (pinfunction "1_1") (pintype "passive"))
      (node (ref "C23") (pin "1") (pinfunction "1_1") (pintype "passive"))
      (node (ref "C83") (pin "1") (pinfunction "1_1") (pintype "passive"))
      (node (ref "C84") (pin "1") (pinfunction "1_1") (pintype "passive"))
      (node (ref "IC10") (pin "4") (pinfunction "VIN-_4") (pintype "input"))
      (node (ref "IC8") (pin "4") (pinfunction "VIN_4") (pintype "bidirectional"))
      (node (ref "JP1") (pin "3") (pinfunction "3_3") (pintype "bidirectional"))
      (node (ref "Q3") (pin "4") (pinfunction "Q2S_4") (pintype "bidirectional"))
      (node (ref "R22") (pin "1") (pinfunction "1_1") (pintype "passive"))
      (node (ref "R33") (pin "2") (pinfunction "2_2") (pintype "passive"))
      (node (ref "R39") (pin "1") (pinfunction "1_1") (pintype "passive"))
      (node (ref "R9") (pin "6") (pinfunction "2_6") (pintype "passive"))
    )
    (net (code "119") (name "unconnected-(IC1-AN8{slash}RPB8{slash}CTED10{slash}RB8-Pad32)") (class "Default")
      (node (ref "IC1") (pin "32") (pinfunction "AN8/RPB8/CTED10/RB8_32") (pintype "bidirectional"))
    )
    (net (code "120") (name "unconnected-(IC1-AN9{slash}RPB9{slash}CTED4{slash}RB9-Pad33)") (class "Default")
      (node (ref "IC1") (pin "33") (pinfunction "AN9/RPB9/CTED4/RB9_33") (pintype "bidirectional"))
    )
    (net (code "121") (name "unconnected-(IC1-AN11{slash}PMA12{slash}RB11-Pad35)") (class "Default")
      (node (ref "IC1") (pin "35") (pinfunction "AN11/PMA12/RB11_35") (pintype "bidirectional"))
    )
    (net (code "122") (name "unconnected-(IC1-AN12{slash}PMA11{slash}RB12-Pad41)") (class "Default")
      (node (ref "IC1") (pin "41") (pinfunction "AN12/PMA11/RB12_41") (pintype "bidirectional"))
    )
    (net (code "123") (name "unconnected-(IC1-AN13{slash}RB13-Pad42)") (class "Default")
      (node (ref "IC1") (pin "42") (pinfunction "AN13/RB13_42") (pintype "bidirectional"))
    )
    (net (code "124") (name "unconnected-(IC1-AN14{slash}RPB14{slash}PMA1{slash}CTED5{slash}RB14-Pad43)") (class "Default")
      (node (ref "IC1") (pin "43") (pinfunction "AN14/RPB14/PMA1/CTED5/RB14_43") (pintype "bidirectional"))
    )
    (net (code "125") (name "unconnected-(IC1-AN15{slash}RPB15{slash}PMA0{slash}CTED6{slash}{slash}RB15-Pad44)") (class "Default")
      (node (ref "IC1") (pin "44") (pinfunction "AN15/RPB15/PMA0/CTED6//RB15_44") (pintype "bidirectional"))
    )
    (net (code "126") (name "unconnected-(IC1-AN20{slash}PMD2{slash}RE2-Pad98)") (class "Default")
      (node (ref "IC1") (pin "98") (pinfunction "AN20/PMD2/RE2_98") (pintype "bidirectional"))
    )
    (net (code "127") (name "unconnected-(IC1-AN21{slash}PMD4{slash}RE4-Pad100)") (class "Default")
      (node (ref "IC1") (pin "100") (pinfunction "AN21/PMD4/RE4_100") (pintype "bidirectional"))
    )
    (net (code "128") (name "unconnected-(IC1-AN22{slash}RPE5{slash}PMD5{slash}RE5-Pad3)") (class "Default")
      (node (ref "IC1") (pin "3") (pinfunction "AN22/RPE5/PMD5/RE5_3") (pintype "bidirectional"))
    )
    (net (code "129") (name "unconnected-(IC1-AN23{slash}PMD6{slash}RE6-Pad4)") (class "Default")
      (node (ref "IC1") (pin "4") (pinfunction "AN23/PMD6/RE6_4") (pintype "bidirectional"))
    )
    (net (code "130") (name "unconnected-(IC1-AN24{slash}RPD1{slash}RD1-Pad76)") (class "Default")
      (node (ref "IC1") (pin "76") (pinfunction "AN24/RPD1/RD1_76") (pintype "bidirectional"))
    )
    (net (code "131") (name "unconnected-(IC1-AN25{slash}RPD2{slash}RD2-Pad77)") (class "Default")
      (node (ref "IC1") (pin "77") (pinfunction "AN25/RPD2/RD2_77") (pintype "bidirectional"))
    )
    (net (code "132") (name "unconnected-(IC1-AN26{slash}RPD3{slash}RD3-Pad78)") (class "Default")
      (node (ref "IC1") (pin "78") (pinfunction "AN26/RPD3/RD3_78") (pintype "bidirectional"))
    )
    (net (code "133") (name "unconnected-(IC1-AN27{slash}PMD7{slash}RE7-Pad5)") (class "Default")
      (node (ref "IC1") (pin "5") (pinfunction "AN27/PMD7/RE7_5") (pintype "bidirectional"))
    )
    (net (code "134") (name "unconnected-(IC1-CVREFOUT{slash}AN10{slash}RPB10{slash}PMA13{slash}CTED11{slash}RB10-Pad34)") (class "Default")
      (node (ref "IC1") (pin "34") (pinfunction "CVREFOUT/AN10/RPB10/PMA13/CTED11/RB10_34") (pintype "bidirectional"))
    )
    (net (code "135") (name "unconnected-(IC1-PGEC3{slash}AN2{slash}C2INB{slash}RPB2{slash}CTED13{slash}RB2-Pad23)") (class "Default")
      (node (ref "IC1") (pin "23") (pinfunction "PGEC3/AN2/C2INB/RPB2/CTED13/RB2_23") (pintype "bidirectional"))
    )
    (net (code "136") (name "unconnected-(IC1-PMD0{slash}RE0-Pad93)") (class "Default")
      (node (ref "IC1") (pin "93") (pinfunction "PMD0/RE0_93") (pintype "bidirectional"))
    )
    (net (code "137") (name "unconnected-(IC1-PMD1{slash}RE1-Pad94)") (class "Default")
      (node (ref "IC1") (pin "94") (pinfunction "PMD1/RE1_94") (pintype "bidirectional"))
    )
    (net (code "138") (name "unconnected-(IC1-PMD13{slash}RD13-Pad80)") (class "Default")
      (node (ref "IC1") (pin "80") (pinfunction "PMD13/RD13_80") (pintype "bidirectional"))
    )
    (net (code "139") (name "unconnected-(IC1-PMD14{slash}RD6-Pad83)") (class "Default")
      (node (ref "IC1") (pin "83") (pinfunction "PMD14/RD6_83") (pintype "bidirectional"))
    )
    (net (code "140") (name "unconnected-(IC1-RPC1{slash}RC1-Pad6)") (class "Default")
      (node (ref "IC1") (pin "6") (pinfunction "RPC1/RC1_6") (pintype "bidirectional"))
    )
    (net (code "141") (name "unconnected-(IC1-RPC2{slash}RC2-Pad7)") (class "Default")
      (node (ref "IC1") (pin "7") (pinfunction "RPC2/RC2_7") (pintype "bidirectional"))
    )
    (net (code "142") (name "unconnected-(IC1-RPC3{slash}RC3-Pad8)") (class "Default")
      (node (ref "IC1") (pin "8") (pinfunction "RPC3/RC3_8") (pintype "bidirectional"))
    )
    (net (code "143") (name "unconnected-(IC1-RPD0{slash}INT0{slash}RD0-Pad72)") (class "Default")
      (node (ref "IC1") (pin "72") (pinfunction "RPD0/INT0/RD0_72") (pintype "bidirectional"))
    )
    (net (code "144") (name "unconnected-(IC1-RPD4{slash}PMWR{slash}RD4-Pad81)") (class "Default")
      (node (ref "IC1") (pin "81") (pinfunction "RPD4/PMWR/RD4_81") (pintype "bidirectional"))
    )
    (net (code "145") (name "unconnected-(IC1-RPD5{slash}PMRD{slash}RD5-Pad82)") (class "Default")
      (node (ref "IC1") (pin "82") (pinfunction "RPD5/PMRD/RD5_82") (pintype "bidirectional"))
    )
    (net (code "146") (name "unconnected-(IC1-RPD8{slash}RTCC{slash}RD8-Pad68)") (class "Default")
      (node (ref "IC1") (pin "68") (pinfunction "RPD8/RTCC/RD8_68") (pintype "bidirectional"))
    )
    (net (code "147") (name "unconnected-(IC1-RPD9{slash}RD9-Pad69)") (class "Default")
      (node (ref "IC1") (pin "69") (pinfunction "RPD9/RD9_69") (pintype "bidirectional"))
    )
    (net (code "148") (name "unconnected-(IC1-RPD10{slash}SCK1{slash}PMCS2{slash}RD10-Pad70)") (class "Default")
      (node (ref "IC1") (pin "70") (pinfunction "RPD10/SCK1/PMCS2/RD10_70") (pintype "bidirectional"))
    )
    (net (code "149") (name "unconnected-(IC1-RPD11{slash}PMCS1{slash}RD11-Pad71)") (class "Default")
      (node (ref "IC1") (pin "71") (pinfunction "RPD11/PMCS1/RD11_71") (pintype "bidirectional"))
    )
    (net (code "150") (name "unconnected-(IC1-RPD12{slash}PMD12{slash}RD12-Pad79)") (class "Default")
      (node (ref "IC1") (pin "79") (pinfunction "RPD12/PMD12/RD12_79") (pintype "bidirectional"))
    )
    (net (code "151") (name "unconnected-(IC1-RPD14{slash}RD14-Pad47)") (class "Default")
      (node (ref "IC1") (pin "47") (pinfunction "RPD14/RD14_47") (pintype "bidirectional"))
    )
    (net (code "152") (name "unconnected-(IC1-RPD15{slash}RD15-Pad48)") (class "Default")
      (node (ref "IC1") (pin "48") (pinfunction "RPD15/RD15_48") (pintype "bidirectional"))
    )
    (net (code "153") (name "unconnected-(IC1-RPE3{slash}PMD3{slash}RE3-Pad99)") (class "Default")
      (node (ref "IC1") (pin "99") (pinfunction "RPE3/PMD3/RE3_99") (pintype "bidirectional"))
    )
    (net (code "154") (name "unconnected-(IC1-RPE8{slash}RE8-Pad18)") (class "Default")
      (node (ref "IC1") (pin "18") (pinfunction "RPE8/RE8_18") (pintype "bidirectional"))
    )
    (net (code "155") (name "unconnected-(IC1-RPE9{slash}RE9-Pad19)") (class "Default")
      (node (ref "IC1") (pin "19") (pinfunction "RPE9/RE9_19") (pintype "bidirectional"))
    )
    (net (code "156") (name "unconnected-(IC1-RPF3{slash}USBID{slash}RF3-Pad51)") (class "Default")
      (node (ref "IC1") (pin "51") (pinfunction "RPF3/USBID/RF3_51") (pintype "bidirectional"))
    )
    (net (code "157") (name "unconnected-(IC1-RPF4{slash}PMA9{slash}RF4-Pad49)") (class "Default")
      (node (ref "IC1") (pin "49") (pinfunction "RPF4/PMA9/RF4_49") (pintype "bidirectional"))
    )
    (net (code "158") (name "unconnected-(IC1-RPF5{slash}PMA8{slash}RF5-Pad50)") (class "Default")
      (node (ref "IC1") (pin "50") (pinfunction "RPF5/PMA8/RF5_50") (pintype "bidirectional"))
    )
    (net (code "159") (name "unconnected-(IC1-RPF12{slash}RF12-Pad40)") (class "Default")
      (node (ref "IC1") (pin "40") (pinfunction "RPF12/RF12_40") (pintype "bidirectional"))
    )
    (net (code "160") (name "unconnected-(IC1-RPF13{slash}RF13-Pad39)") (class "Default")
      (node (ref "IC1") (pin "39") (pinfunction "RPF13/RF13_39") (pintype "bidirectional"))
    )
    (net (code "161") (name "unconnected-(IC1-RPG0{slash}PMD8{slash}RG0-Pad90)") (class "Default")
      (node (ref "IC1") (pin "90") (pinfunction "RPG0/PMD8/RG0_90") (pintype "bidirectional"))
    )
    (net (code "162") (name "unconnected-(IC1-RPG1{slash}PMD9{slash}RG1-Pad89)") (class "Default")
      (node (ref "IC1") (pin "89") (pinfunction "RPG1/PMD9/RG1_89") (pintype "bidirectional"))
    )
    (net (code "163") (name "unconnected-(IC1-SCL2{slash}RA2-Pad58)") (class "Default")
      (node (ref "IC1") (pin "58") (pinfunction "SCL2/RA2_58") (pintype "bidirectional"))
    )
    (net (code "164") (name "unconnected-(IC1-SDA2{slash}RA3-Pad59)") (class "Default")
      (node (ref "IC1") (pin "59") (pinfunction "SDA2/RA3_59") (pintype "bidirectional"))
    )
    (net (code "165") (name "unconnected-(IC1-SOSCI{slash}RPC13{slash}RC13-Pad73)") (class "Default")
      (node (ref "IC1") (pin "73") (pinfunction "SOSCI/RPC13/RC13_73") (pintype "bidirectional"))
    )
    (net (code "166") (name "unconnected-(IC1-SOSCO{slash}RPC14{slash}T1CK{slash}RC14-Pad74)") (class "Default")
      (node (ref "IC1") (pin "74") (pinfunction "SOSCO/RPC14/T1CK/RC14_74") (pintype "bidirectional"))
    )
    (net (code "167") (name "unconnected-(IC1-TCK{slash}CTED2{slash}RA1-Pad38)") (class "Default")
      (node (ref "IC1") (pin "38") (pinfunction "TCK/CTED2/RA1_38") (pintype "bidirectional"))
    )
    (net (code "168") (name "unconnected-(IC1-TDI{slash}CTED9{slash}RA4-Pad60)") (class "Default")
      (node (ref "IC1") (pin "60") (pinfunction "TDI/CTED9/RA4_60") (pintype "bidirectional"))
    )
    (net (code "169") (name "unconnected-(IC1-TDO{slash}RA5-Pad61)") (class "Default")
      (node (ref "IC1") (pin "61") (pinfunction "TDO/RA5_61") (pintype "bidirectional"))
    )
    (net (code "170") (name "unconnected-(IC1-TMS{slash}CTED1{slash}RA0-Pad17)") (class "Default")
      (node (ref "IC1") (pin "17") (pinfunction "TMS/CTED1/RA0_17") (pintype "bidirectional"))
    )
    (net (code "171") (name "unconnected-(IC1-TRCLK{slash}RA6-Pad91)") (class "Default")
      (node (ref "IC1") (pin "91") (pinfunction "TRCLK/RA6_91") (pintype "bidirectional"))
    )
    (net (code "172") (name "unconnected-(IC1-TRD0{slash}RG13-Pad97)") (class "Default")
      (node (ref "IC1") (pin "97") (pinfunction "TRD0/RG13_97") (pintype "bidirectional"))
    )
    (net (code "173") (name "unconnected-(IC1-TRD2{slash}RG14-Pad95)") (class "Default")
      (node (ref "IC1") (pin "95") (pinfunction "TRD2/RG14_95") (pintype "bidirectional"))
    )
    (net (code "174") (name "unconnected-(IC1-TRD3{slash}CTED8{slash}RA7-Pad92)") (class "Default")
      (node (ref "IC1") (pin "92") (pinfunction "TRD3/CTED8/RA7_92") (pintype "bidirectional"))
    )
    (net (code "175") (name "unconnected-(IC8-PG-Pad9)") (class "Default")
      (node (ref "IC8") (pin "9") (pinfunction "PG_9") (pintype "bidirectional"))
    )
    (net (code "176") (name "unconnected-(Q1A-D-Pad6)") (class "Default")
      (node (ref "Q1") (pin "6") (pinfunction "D_6") (pintype "passive"))
    )
    (net (code "177") (name "unconnected-(Q1A-D1-PadP1)") (class "Default")
      (node (ref "Q1") (pin "P1") (pinfunction "D1_P1") (pintype "passive"))
    )
    (net (code "178") (name "unconnected-(Q1A-G-Pad2)") (class "Default")
      (node (ref "Q1") (pin "2") (pinfunction "G_2") (pintype "passive"))
    )
    (net (code "179") (name "unconnected-(Q1A-S-Pad1)") (class "Default")
      (node (ref "Q1") (pin "1") (pinfunction "S_1") (pintype "passive"))
    )
    (net (code "180") (name "unconnected-(Q2A-D-Pad6)") (class "Default")
      (node (ref "Q2") (pin "6") (pinfunction "D_6") (pintype "passive"))
    )
    (net (code "181") (name "unconnected-(Q2A-D1-PadP1)") (class "Default")
      (node (ref "Q2") (pin "P1") (pinfunction "D1_P1") (pintype "passive"))
    )
    (net (code "182") (name "unconnected-(Q2A-G-Pad2)") (class "Default")
      (node (ref "Q2") (pin "2") (pinfunction "G_2") (pintype "passive"))
    )
    (net (code "183") (name "unconnected-(Q2A-S-Pad1)") (class "Default")
      (node (ref "Q2") (pin "1") (pinfunction "S_1") (pintype "passive"))
    )
  )
)
